# WC.net
KiCad netlist of a schematic drawn in EAGLE
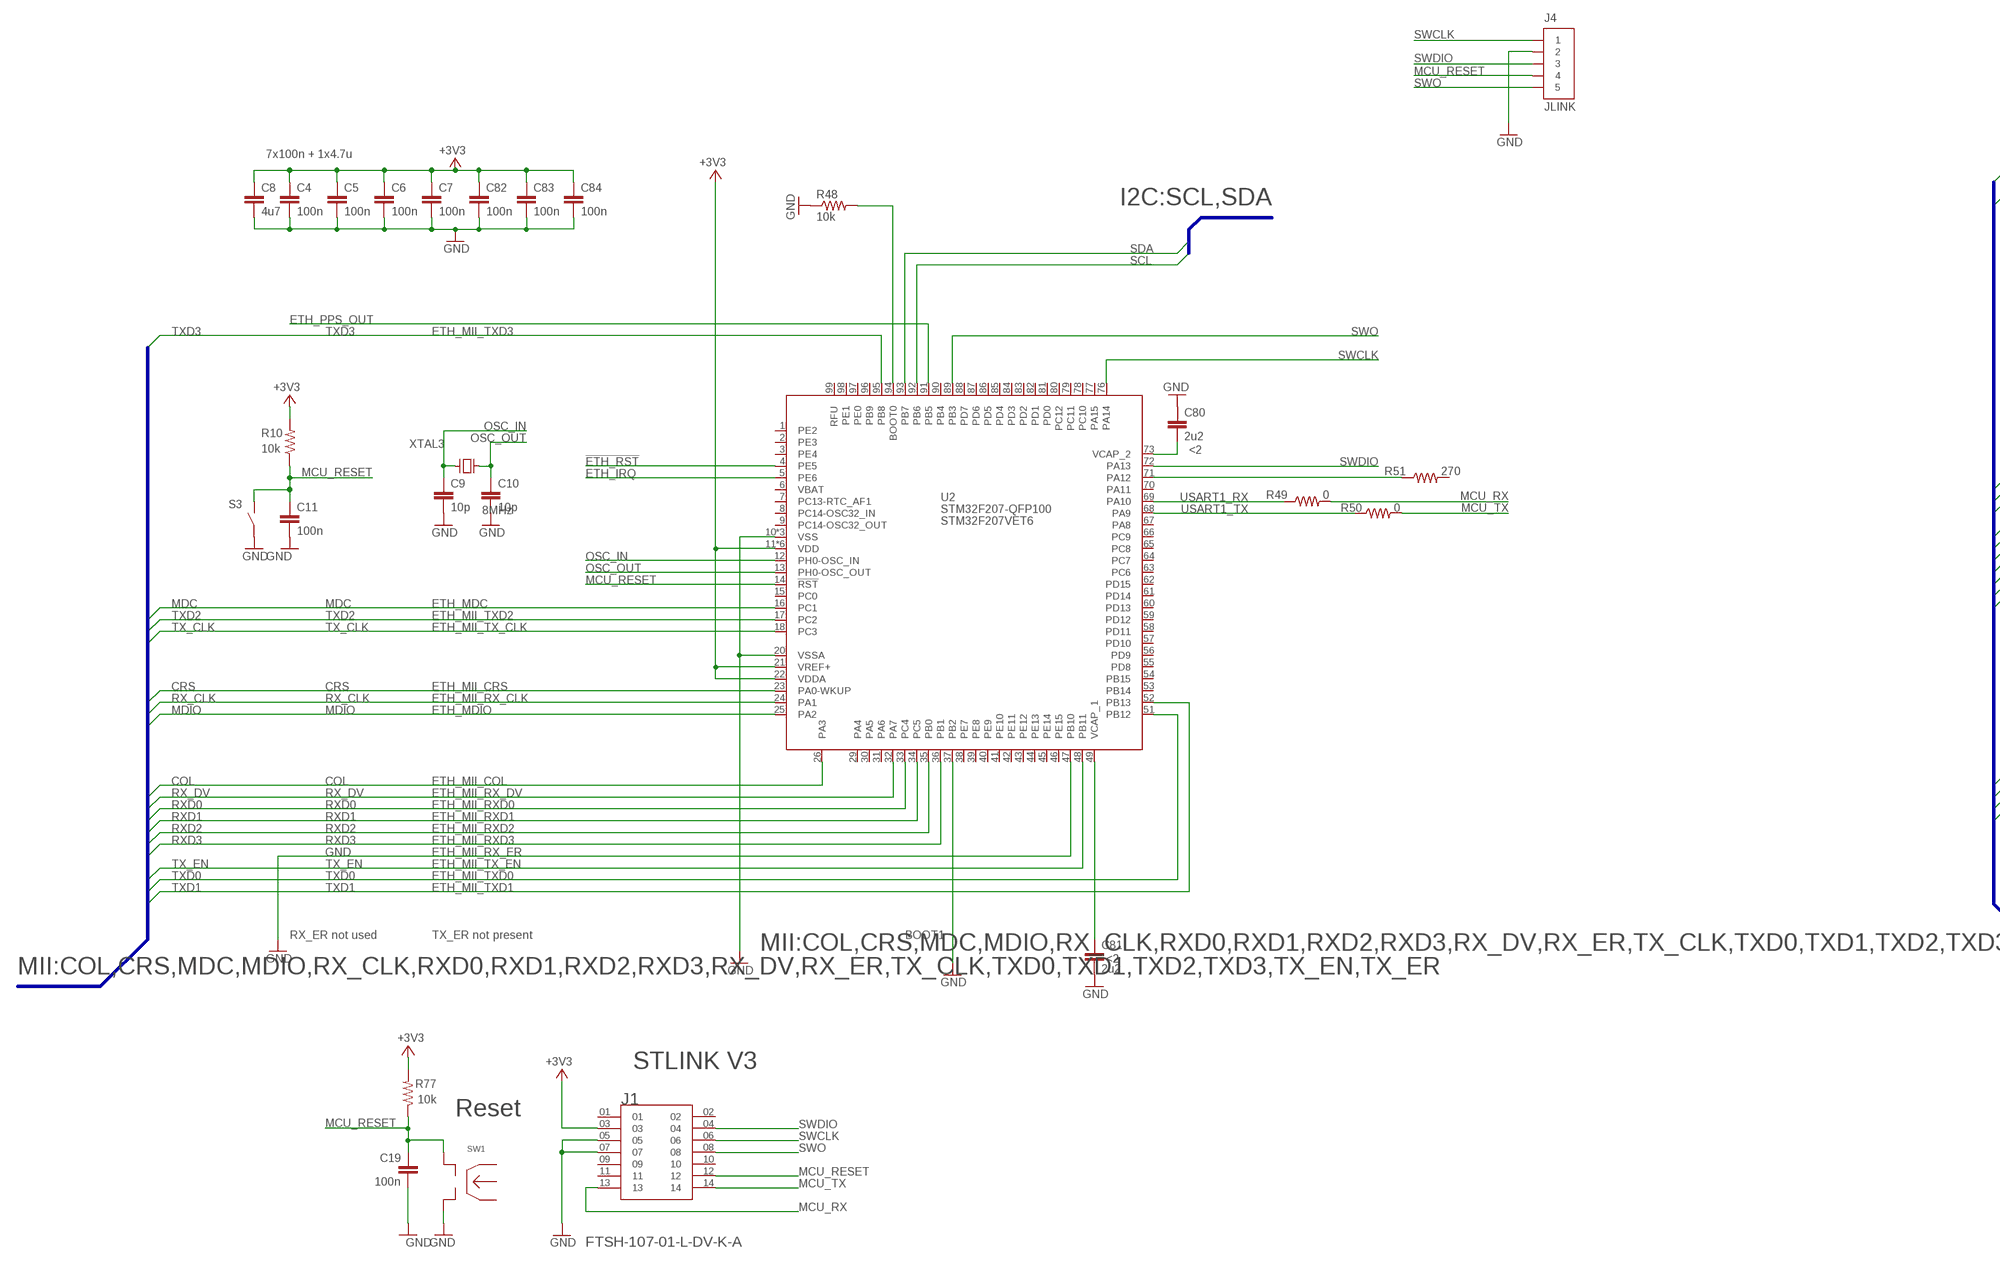
[diagram p0: schematic, sheet 1, part 1 of 2]
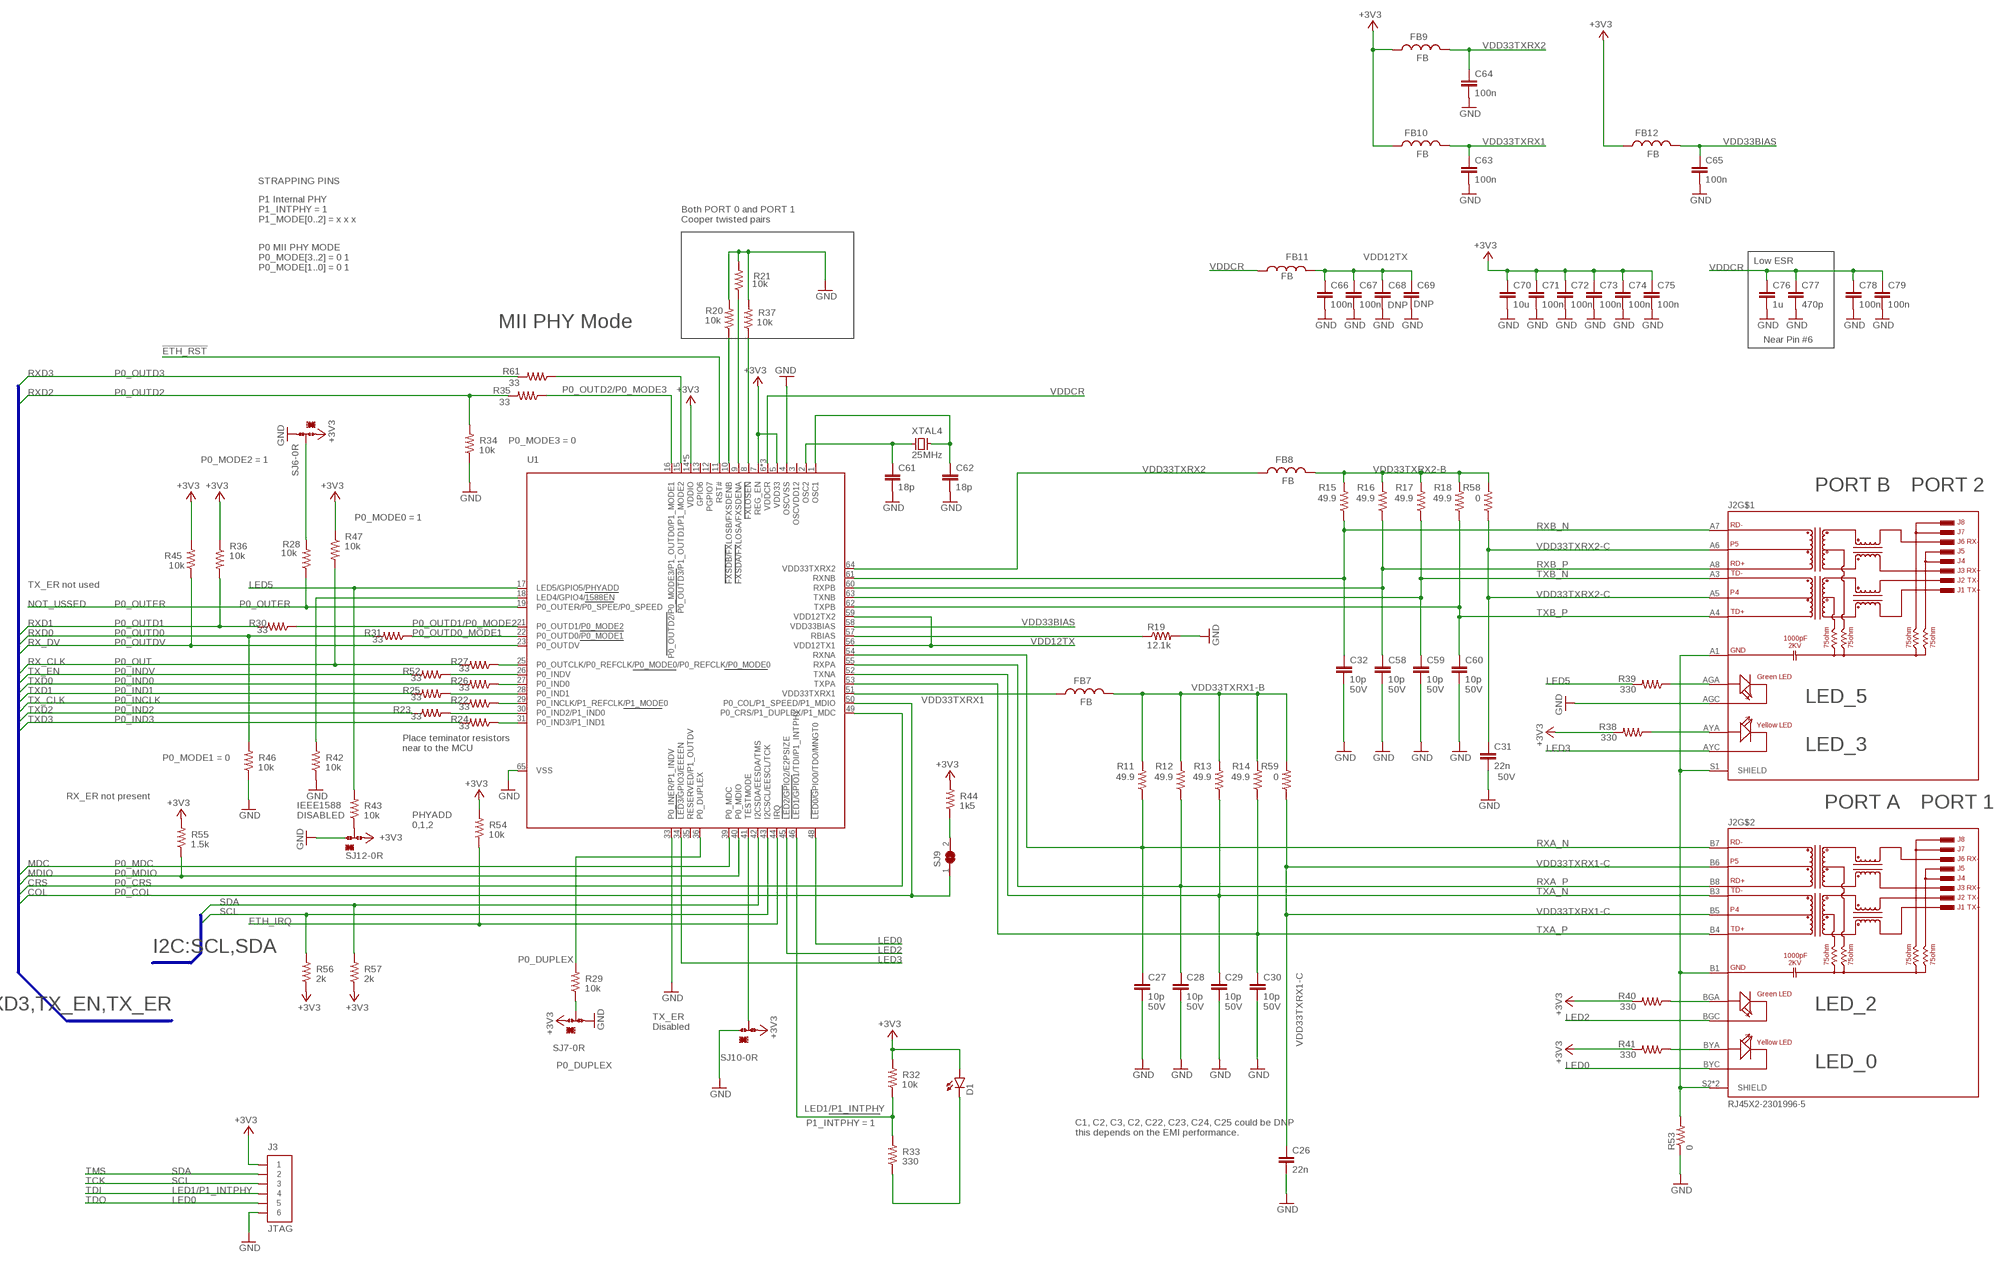
[diagram p1: schematic, sheet 1, part 2 of 2]
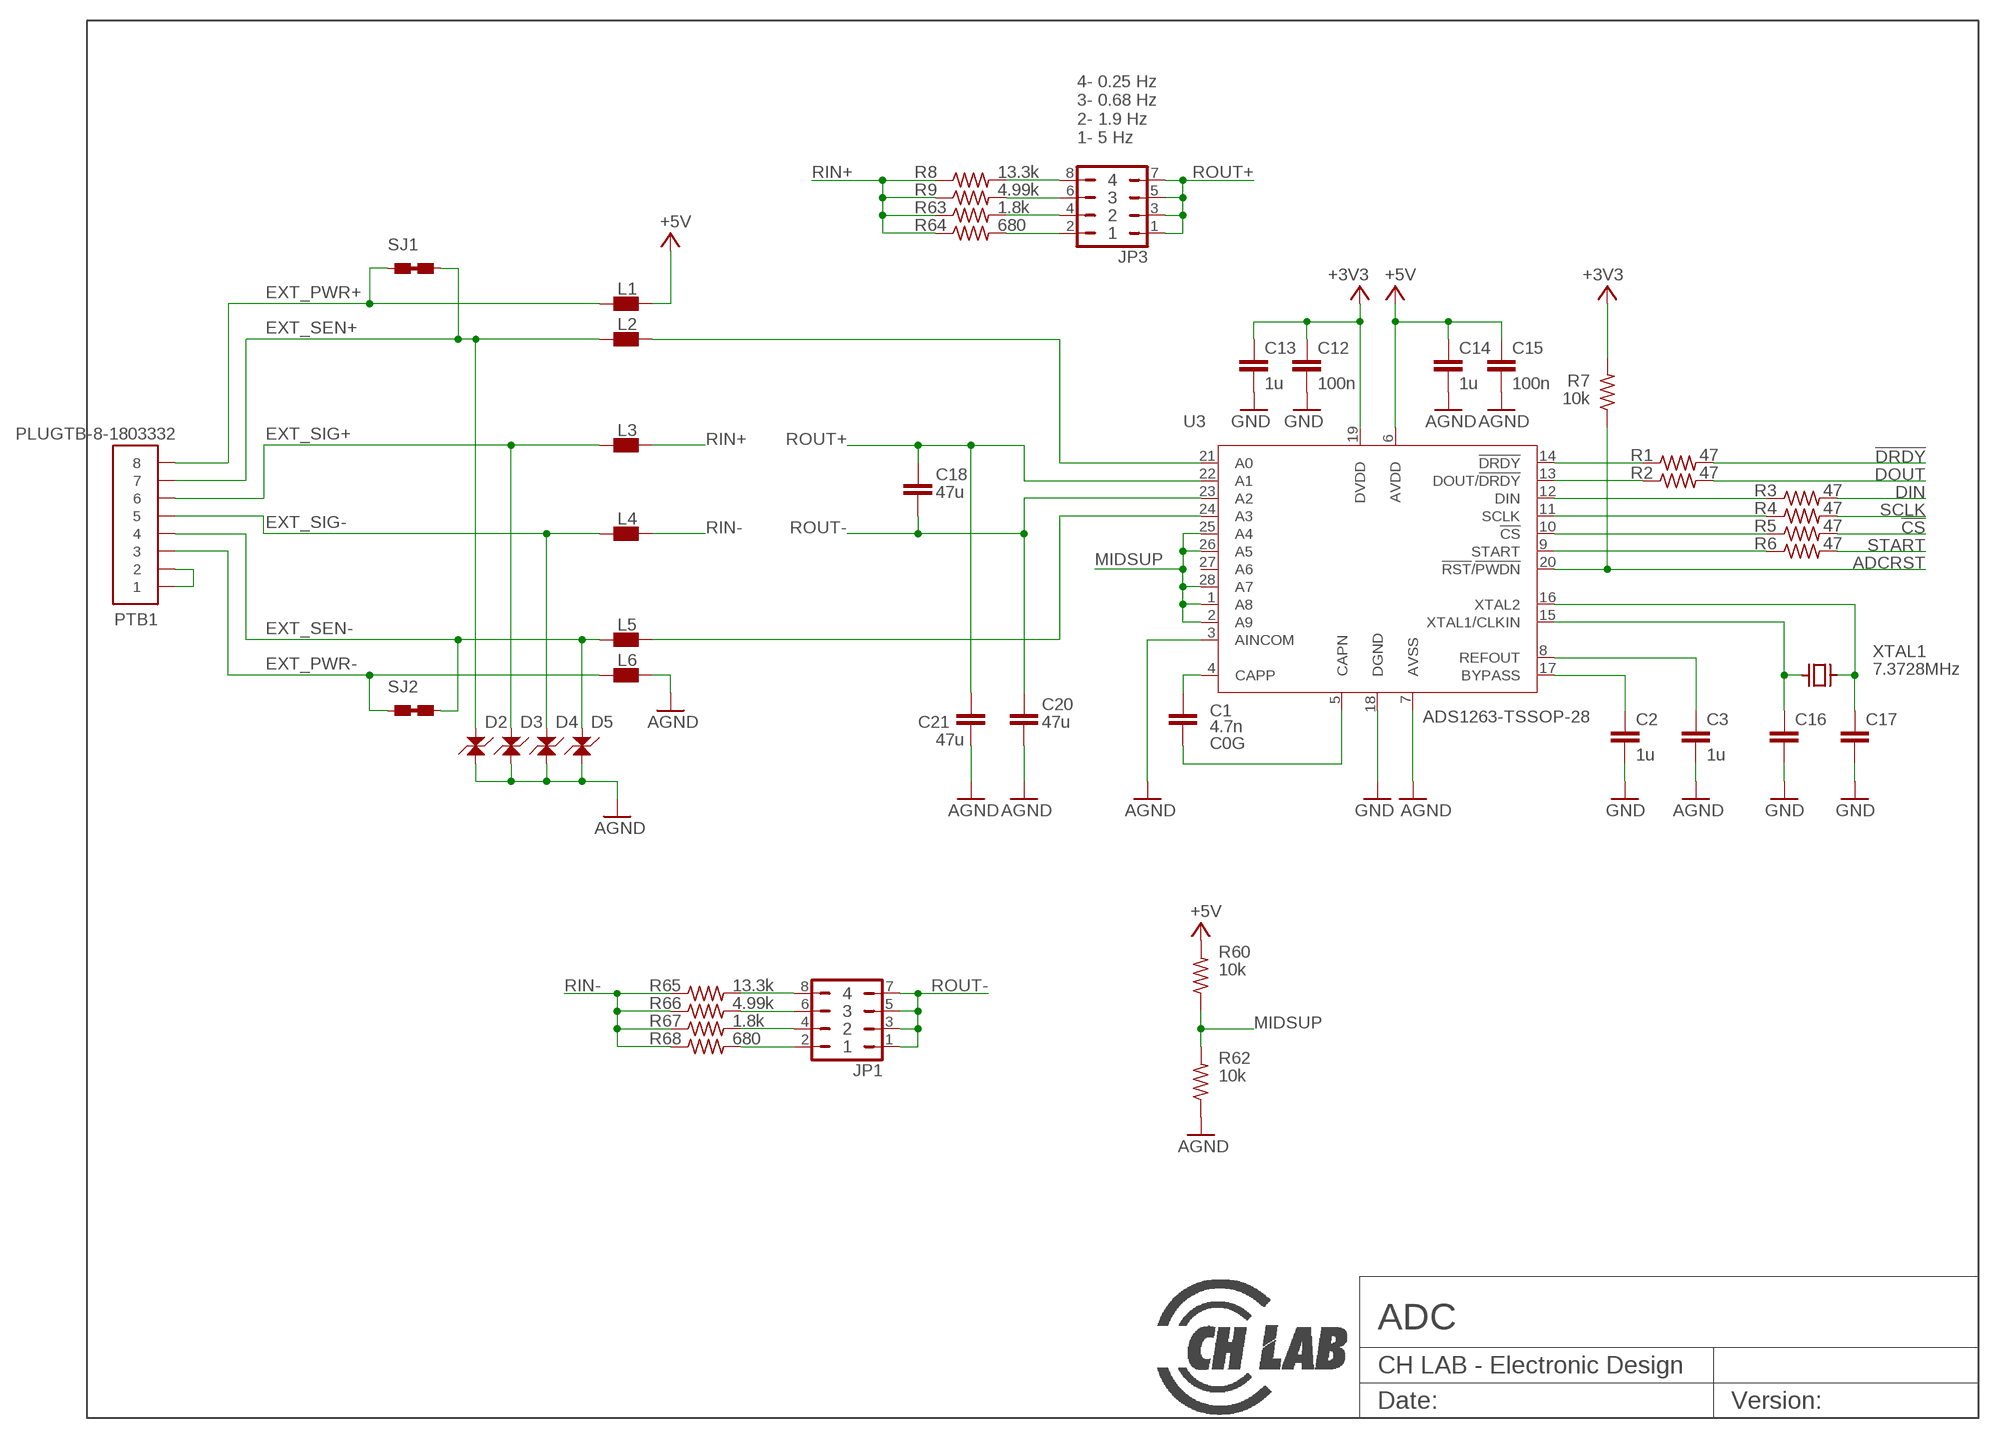
[diagram p2: schematic, sheet 2]

(export (version "E")
  (design (tool "Eeschema 10.0.6"))
  (components
    (comp (ref "C1")
      (value "4.7n")
      (footprint "eagle-import:C_0603")
      (fields (field (name "DK") "C0G"))
      (libsource (lib "eagle-import") (part "C_0603"))
    )
    (comp (ref "C2")
      (value "1u")
      (footprint "eagle-import:C_0603")
      (libsource (lib "eagle-import") (part "C_0603"))
    )
    (comp (ref "C3")
      (value "1u")
      (footprint "eagle-import:C_0603")
      (libsource (lib "eagle-import") (part "C_0603"))
    )
    (comp (ref "C12")
      (value "100n")
      (footprint "eagle-import:C_0603")
      (libsource (lib "eagle-import") (part "C_0603"))
    )
    (comp (ref "C13")
      (value "1u")
      (footprint "eagle-import:C_0603")
      (libsource (lib "eagle-import") (part "C_0603"))
    )
    (comp (ref "C14")
      (value "1u")
      (footprint "eagle-import:C_0603")
      (libsource (lib "eagle-import") (part "C_0603"))
    )
    (comp (ref "C15")
      (value "100n")
      (footprint "eagle-import:C_0603")
      (libsource (lib "eagle-import") (part "C_0603"))
    )
    (comp (ref "C16")
      (value "C_0603")
      (footprint "eagle-import:C_0603")
      (libsource (lib "eagle-import") (part "C_0603"))
    )
    (comp (ref "C17")
      (value "C_0603")
      (footprint "eagle-import:C_0603")
      (libsource (lib "eagle-import") (part "C_0603"))
    )
    (comp (ref "C18")
      (value "47u")
      (footprint "eagle-import:C_1210")
      (libsource (lib "eagle-import") (part "C_1210"))
    )
    (comp (ref "C20")
      (value "47u")
      (footprint "eagle-import:C_1210")
      (libsource (lib "eagle-import") (part "C_1210"))
    )
    (comp (ref "C21")
      (value "47u")
      (footprint "eagle-import:C_1210")
      (libsource (lib "eagle-import") (part "C_1210"))
    )
    (comp (ref "D2")
      (value "LESD5D5.0CT1G")
      (footprint "eagle-import:SOD523")
      (libsource (lib "eagle-import") (part "LESD5D5.0CT1G"))
    )
    (comp (ref "D3")
      (value "LESD5D5.0CT1G")
      (footprint "eagle-import:SOD523")
      (libsource (lib "eagle-import") (part "LESD5D5.0CT1G"))
    )
    (comp (ref "D4")
      (value "LESD5D5.0CT1G")
      (footprint "eagle-import:SOD523")
      (libsource (lib "eagle-import") (part "LESD5D5.0CT1G"))
    )
    (comp (ref "D5")
      (value "LESD5D5.0CT1G")
      (footprint "eagle-import:SOD523")
      (libsource (lib "eagle-import") (part "LESD5D5.0CT1G"))
    )
    (comp (ref "JP1")
      (value "JP4Q")
      (footprint "eagle-import:JP4Q")
      (libsource (lib "eagle-import") (part "JP4Q"))
    )
    (comp (ref "JP3")
      (value "JP4Q")
      (footprint "eagle-import:JP4Q")
      (libsource (lib "eagle-import") (part "JP4Q"))
    )
    (comp (ref "L1")
      (value "FB_0603")
      (footprint "eagle-import:R_0603")
      (libsource (lib "eagle-import") (part "FB_0603"))
    )
    (comp (ref "L2")
      (value "FB_0603")
      (footprint "eagle-import:R_0603")
      (libsource (lib "eagle-import") (part "FB_0603"))
    )
    (comp (ref "L3")
      (value "FB_0603")
      (footprint "eagle-import:R_0603")
      (libsource (lib "eagle-import") (part "FB_0603"))
    )
    (comp (ref "L4")
      (value "FB_0603")
      (footprint "eagle-import:R_0603")
      (libsource (lib "eagle-import") (part "FB_0603"))
    )
    (comp (ref "L5")
      (value "FB_0603")
      (footprint "eagle-import:R_0603")
      (libsource (lib "eagle-import") (part "FB_0603"))
    )
    (comp (ref "L6")
      (value "FB_0603")
      (footprint "eagle-import:R_0603")
      (libsource (lib "eagle-import") (part "FB_0603"))
    )
    (comp (ref "PTB1")
      (value "PLUGTB-8-1803332")
      (footprint "eagle-import:1803332")
      (libsource (lib "eagle-import") (part "PLUGTB-8-1803332"))
    )
    (comp (ref "R1")
      (value "47")
      (footprint "eagle-import:R_0402")
      (libsource (lib "eagle-import") (part "R_0402"))
    )
    (comp (ref "R2")
      (value "47")
      (footprint "eagle-import:R_0402")
      (libsource (lib "eagle-import") (part "R_0402"))
    )
    (comp (ref "R3")
      (value "47")
      (footprint "eagle-import:R_0402")
      (libsource (lib "eagle-import") (part "R_0402"))
    )
    (comp (ref "R4")
      (value "47")
      (footprint "eagle-import:R_0402")
      (libsource (lib "eagle-import") (part "R_0402"))
    )
    (comp (ref "R5")
      (value "47")
      (footprint "eagle-import:R_0402")
      (libsource (lib "eagle-import") (part "R_0402"))
    )
    (comp (ref "R6")
      (value "47")
      (footprint "eagle-import:R_0402")
      (libsource (lib "eagle-import") (part "R_0402"))
    )
    (comp (ref "R7")
      (value "10k")
      (footprint "eagle-import:R_0603")
      (libsource (lib "eagle-import") (part "R_0603"))
    )
    (comp (ref "R8")
      (value "13.3k")
      (footprint "eagle-import:R_0603")
      (libsource (lib "eagle-import") (part "R_0603"))
    )
    (comp (ref "R9")
      (value "4.99k")
      (footprint "eagle-import:R_0603")
      (libsource (lib "eagle-import") (part "R_0603"))
    )
    (comp (ref "R60")
      (value "10k")
      (footprint "eagle-import:R_0603")
      (libsource (lib "eagle-import") (part "R_0603"))
    )
    (comp (ref "R62")
      (value "10k")
      (footprint "eagle-import:R_0603")
      (libsource (lib "eagle-import") (part "R_0603"))
    )
    (comp (ref "R63")
      (value "1.8k")
      (footprint "eagle-import:R_0603")
      (libsource (lib "eagle-import") (part "R_0603"))
    )
    (comp (ref "R64")
      (value "680")
      (footprint "eagle-import:R_0603")
      (libsource (lib "eagle-import") (part "R_0603"))
    )
    (comp (ref "R65")
      (value "13.3k")
      (footprint "eagle-import:R_0603")
      (libsource (lib "eagle-import") (part "R_0603"))
    )
    (comp (ref "R66")
      (value "4.99k")
      (footprint "eagle-import:R_0603")
      (libsource (lib "eagle-import") (part "R_0603"))
    )
    (comp (ref "R67")
      (value "1.8k")
      (footprint "eagle-import:R_0603")
      (libsource (lib "eagle-import") (part "R_0603"))
    )
    (comp (ref "R68")
      (value "680")
      (footprint "eagle-import:R_0603")
      (libsource (lib "eagle-import") (part "R_0603"))
    )
    (comp (ref "SJ1")
      (value "SJUMPER-NC")
      (footprint "eagle-import:SJ1")
      (libsource (lib "eagle-import") (part "SJUMPER-NC"))
    )
    (comp (ref "SJ2")
      (value "SJUMPER-NC")
      (footprint "eagle-import:SJ1")
      (libsource (lib "eagle-import") (part "SJUMPER-NC"))
    )
    (comp (ref "U3")
      (value "ADS1263-TSSOP-28")
      (footprint "eagle-import:SOP65P640X120-28N")
      (libsource (lib "eagle-import") (part "ADS1263-TSSOP-28"))
    )
    (comp (ref "XTAL1")
      (value "7.3728MHz")
      (footprint "eagle-import:XTAL")
      (fields
        (field (name "LINK") "https://www.mouser.com/ProductDetail/ABRACON/ABLS-7.3728MHZ-K4T?qs=uDmhV2jwPReaiEAs5bxjfg%3D%3D")
        (field (name "MPN") "ABLS-7.3728MHZ-K4T")
      )
      (libsource (lib "eagle-import") (part "XTAL-SMD-11.44.8"))
    )
    (comp (ref "C4")
      (value "100n")
      (footprint "eagle-import:C_0603")
      (libsource (lib "eagle-import") (part "C_0603"))
    )
    (comp (ref "C5")
      (value "100n")
      (footprint "eagle-import:C_0603")
      (libsource (lib "eagle-import") (part "C_0603"))
    )
    (comp (ref "C6")
      (value "100n")
      (footprint "eagle-import:C_0603")
      (libsource (lib "eagle-import") (part "C_0603"))
    )
    (comp (ref "C7")
      (value "100n")
      (footprint "eagle-import:C_0603")
      (libsource (lib "eagle-import") (part "C_0603"))
    )
    (comp (ref "C8")
      (value "4u7")
      (footprint "eagle-import:C_0805")
      (libsource (lib "eagle-import") (part "C_0805"))
    )
    (comp (ref "C9")
      (value "10p")
      (footprint "eagle-import:C_0603")
      (libsource (lib "eagle-import") (part "C_0603"))
    )
    (comp (ref "C10")
      (value "10p")
      (footprint "eagle-import:C_0603")
      (libsource (lib "eagle-import") (part "C_0603"))
    )
    (comp (ref "C11")
      (value "100n")
      (footprint "eagle-import:C_0603")
      (libsource (lib "eagle-import") (part "C_0603"))
    )
    (comp (ref "C19")
      (value "100n")
      (footprint "eagle-import:C_0603")
      (libsource (lib "eagle-import") (part "C_0603"))
    )
    (comp (ref "C26")
      (value "22n")
      (footprint "eagle-import:C_0805")
      (libsource (lib "eagle-import") (part "C_0805"))
    )
    (comp (ref "C27")
      (value "10p")
      (footprint "eagle-import:C_0402")
      (fields (field (name "V") "50V"))
      (libsource (lib "eagle-import") (part "C_0402"))
    )
    (comp (ref "C28")
      (value "10p")
      (footprint "eagle-import:C_0402")
      (fields (field (name "V") "50V"))
      (libsource (lib "eagle-import") (part "C_0402"))
    )
    (comp (ref "C29")
      (value "10p")
      (footprint "eagle-import:C_0402")
      (fields (field (name "V") "50V"))
      (libsource (lib "eagle-import") (part "C_0402"))
    )
    (comp (ref "C30")
      (value "10p")
      (footprint "eagle-import:C_0402")
      (fields (field (name "V") "50V"))
      (libsource (lib "eagle-import") (part "C_0402"))
    )
    (comp (ref "C31")
      (value "22n")
      (footprint "eagle-import:C_0805")
      (fields (field (name "VOLTAGE") "50V"))
      (libsource (lib "eagle-import") (part "C_0805"))
    )
    (comp (ref "C32")
      (value "10p")
      (footprint "eagle-import:C_0402")
      (fields (field (name "V") "50V"))
      (libsource (lib "eagle-import") (part "C_0402"))
    )
    (comp (ref "C58")
      (value "10p")
      (footprint "eagle-import:C_0402")
      (fields (field (name "V") "50V"))
      (libsource (lib "eagle-import") (part "C_0402"))
    )
    (comp (ref "C59")
      (value "10p")
      (footprint "eagle-import:C_0402")
      (fields (field (name "V") "50V"))
      (libsource (lib "eagle-import") (part "C_0402"))
    )
    (comp (ref "C60")
      (value "10p")
      (footprint "eagle-import:C_0402")
      (fields (field (name "V") "50V"))
      (libsource (lib "eagle-import") (part "C_0402"))
    )
    (comp (ref "C61")
      (value "18p")
      (footprint "eagle-import:C_0603")
      (libsource (lib "eagle-import") (part "C_0603"))
    )
    (comp (ref "C62")
      (value "18p")
      (footprint "eagle-import:C_0603")
      (libsource (lib "eagle-import") (part "C_0603"))
    )
    (comp (ref "C63")
      (value "100n")
      (footprint "eagle-import:C_0603")
      (libsource (lib "eagle-import") (part "C_0603"))
    )
    (comp (ref "C64")
      (value "100n")
      (footprint "eagle-import:C_0603")
      (libsource (lib "eagle-import") (part "C_0603"))
    )
    (comp (ref "C65")
      (value "100n")
      (footprint "eagle-import:C_0603")
      (libsource (lib "eagle-import") (part "C_0603"))
    )
    (comp (ref "C66")
      (value "100n")
      (footprint "eagle-import:C_0603")
      (libsource (lib "eagle-import") (part "C_0603"))
    )
    (comp (ref "C67")
      (value "100n")
      (footprint "eagle-import:C_0603")
      (libsource (lib "eagle-import") (part "C_0603"))
    )
    (comp (ref "C68")
      (value "100n")
      (footprint "eagle-import:C_0603")
      (fields (field (name "DNP") "DNP"))
      (libsource (lib "eagle-import") (part "C_0603"))
    )
    (comp (ref "C69")
      (value "100n")
      (footprint "eagle-import:C_0603")
      (fields (field (name "DNP") "DNP"))
      (libsource (lib "eagle-import") (part "C_0603"))
    )
    (comp (ref "C70")
      (value "10u")
      (footprint "eagle-import:C_0603")
      (libsource (lib "eagle-import") (part "C_0603"))
    )
    (comp (ref "C71")
      (value "100n")
      (footprint "eagle-import:C_0603")
      (libsource (lib "eagle-import") (part "C_0603"))
    )
    (comp (ref "C72")
      (value "100n")
      (footprint "eagle-import:C_0603")
      (libsource (lib "eagle-import") (part "C_0603"))
    )
    (comp (ref "C73")
      (value "100n")
      (footprint "eagle-import:C_0603")
      (libsource (lib "eagle-import") (part "C_0603"))
    )
    (comp (ref "C74")
      (value "100n")
      (footprint "eagle-import:C_0603")
      (libsource (lib "eagle-import") (part "C_0603"))
    )
    (comp (ref "C75")
      (value "100n")
      (footprint "eagle-import:C_0603")
      (libsource (lib "eagle-import") (part "C_0603"))
    )
    (comp (ref "C76")
      (value "1u")
      (footprint "eagle-import:C_0603")
      (fields (field (name "ERS") "LOW"))
      (libsource (lib "eagle-import") (part "C_0603"))
    )
    (comp (ref "C77")
      (value "470p")
      (footprint "eagle-import:C_0603")
      (libsource (lib "eagle-import") (part "C_0603"))
    )
    (comp (ref "C78")
      (value "100n")
      (footprint "eagle-import:C_0603")
      (libsource (lib "eagle-import") (part "C_0603"))
    )
    (comp (ref "C79")
      (value "100n")
      (footprint "eagle-import:C_0603")
      (libsource (lib "eagle-import") (part "C_0603"))
    )
    (comp (ref "C80")
      (value "2u2")
      (footprint "eagle-import:C_0603")
      (fields (field (name "ERS") "<2"))
      (libsource (lib "eagle-import") (part "C_0603"))
    )
    (comp (ref "C81")
      (value "2u2")
      (footprint "eagle-import:C_0603")
      (fields (field (name "ERS") "<2"))
      (libsource (lib "eagle-import") (part "C_0603"))
    )
    (comp (ref "C82")
      (value "100n")
      (footprint "eagle-import:C_0603")
      (libsource (lib "eagle-import") (part "C_0603"))
    )
    (comp (ref "C83")
      (value "100n")
      (footprint "eagle-import:C_0603")
      (libsource (lib "eagle-import") (part "C_0603"))
    )
    (comp (ref "C84")
      (value "100n")
      (footprint "eagle-import:C_0603")
      (libsource (lib "eagle-import") (part "C_0603"))
    )
    (comp (ref "D1")
      (value "LED_0603_ARROW")
      (footprint "eagle-import:LED_0603_ARROW")
      (libsource (lib "eagle-import") (part "LED_0603_ARROW"))
    )
    (comp (ref "FB7")
      (value "FB")
      (footprint "eagle-import:L_0603")
      (libsource (lib "eagle-import") (part "L_0603"))
    )
    (comp (ref "FB8")
      (value "FB")
      (footprint "eagle-import:L_0603")
      (libsource (lib "eagle-import") (part "L_0603"))
    )
    (comp (ref "FB9")
      (value "FB")
      (footprint "eagle-import:L_0603")
      (libsource (lib "eagle-import") (part "L_0603"))
    )
    (comp (ref "FB10")
      (value "FB")
      (footprint "eagle-import:L_0603")
      (libsource (lib "eagle-import") (part "L_0603"))
    )
    (comp (ref "FB11")
      (value "FB")
      (footprint "eagle-import:L_0603")
      (libsource (lib "eagle-import") (part "L_0603"))
    )
    (comp (ref "FB12")
      (value "FB")
      (footprint "eagle-import:L_0603")
      (libsource (lib "eagle-import") (part "L_0603"))
    )
    (comp (ref "J1")
      (value "FTSH-107-01-L-DV-K-A")
      (footprint "eagle-import:SAMTEC_FTSH-107-01-L-DV-K-A")
      (fields (field (name "MANUFACTURER") "Samtec"))
      (libsource (lib "eagle-import") (part "FTSH-107-01-L-DV-K-A"))
    )
    (comp (ref "J2")
      (value "RJ45X2-2301996-5")
      (footprint "eagle-import:2301996-5")
      (libsource (lib "eagle-import") (part "RJ45X2-2301996-5"))
    )
    (comp (ref "J3")
      (value "JTAG")
      (footprint "eagle-import:CONN-VERT-2.54MM-6PINS-2ROWS")
      (libsource (lib "eagle-import") (part "CONVERT-2X3-2.54MM-MALE2.54MM"))
    )
    (comp (ref "J4")
      (value "CONVERT-1X5-2.54MM-MALE_HOLES")
      (footprint "eagle-import:1X05")
      (libsource (lib "eagle-import") (part "CONVERT-1X5-2.54MM-MALE_HOLES"))
    )
    (comp (ref "R10")
      (value "10k")
      (footprint "eagle-import:R_0603")
      (libsource (lib "eagle-import") (part "R_0603"))
    )
    (comp (ref "R11")
      (value "49.9")
      (footprint "eagle-import:R_0402")
      (libsource (lib "eagle-import") (part "R_0402"))
    )
    (comp (ref "R12")
      (value "49.9")
      (footprint "eagle-import:R_0402")
      (libsource (lib "eagle-import") (part "R_0402"))
    )
    (comp (ref "R13")
      (value "49.9")
      (footprint "eagle-import:R_0402")
      (libsource (lib "eagle-import") (part "R_0402"))
    )
    (comp (ref "R14")
      (value "49.9")
      (footprint "eagle-import:R_0402")
      (libsource (lib "eagle-import") (part "R_0402"))
    )
    (comp (ref "R15")
      (value "49.9")
      (footprint "eagle-import:R_0402")
      (libsource (lib "eagle-import") (part "R_0402"))
    )
    (comp (ref "R16")
      (value "49.9")
      (footprint "eagle-import:R_0402")
      (libsource (lib "eagle-import") (part "R_0402"))
    )
    (comp (ref "R17")
      (value "49.9")
      (footprint "eagle-import:R_0402")
      (libsource (lib "eagle-import") (part "R_0402"))
    )
    (comp (ref "R18")
      (value "49.9")
      (footprint "eagle-import:R_0402")
      (libsource (lib "eagle-import") (part "R_0402"))
    )
    (comp (ref "R19")
      (value "12.1k")
      (footprint "eagle-import:R_0603")
      (libsource (lib "eagle-import") (part "R_0603"))
    )
    (comp (ref "R20")
      (value "10k")
      (footprint "eagle-import:R_0603")
      (libsource (lib "eagle-import") (part "R_0603"))
    )
    (comp (ref "R21")
      (value "10k")
      (footprint "eagle-import:R_0603")
      (libsource (lib "eagle-import") (part "R_0603"))
    )
    (comp (ref "R22")
      (value "33")
      (footprint "eagle-import:R_0603")
      (libsource (lib "eagle-import") (part "R_0603"))
    )
    (comp (ref "R23")
      (value "33")
      (footprint "eagle-import:R_0603")
      (libsource (lib "eagle-import") (part "R_0603"))
    )
    (comp (ref "R24")
      (value "33")
      (footprint "eagle-import:R_0603")
      (libsource (lib "eagle-import") (part "R_0603"))
    )
    (comp (ref "R25")
      (value "33")
      (footprint "eagle-import:R_0603")
      (libsource (lib "eagle-import") (part "R_0603"))
    )
    (comp (ref "R26")
      (value "33")
      (footprint "eagle-import:R_0603")
      (libsource (lib "eagle-import") (part "R_0603"))
    )
    (comp (ref "R27")
      (value "33")
      (footprint "eagle-import:R_0603")
      (libsource (lib "eagle-import") (part "R_0603"))
    )
    (comp (ref "R28")
      (value "10k")
      (footprint "eagle-import:R_0603")
      (libsource (lib "eagle-import") (part "R_0603"))
    )
    (comp (ref "R29")
      (value "10k")
      (footprint "eagle-import:R_0603")
      (libsource (lib "eagle-import") (part "R_0603"))
    )
    (comp (ref "R30")
      (value "33")
      (footprint "eagle-import:R_0603")
      (libsource (lib "eagle-import") (part "R_0603"))
    )
    (comp (ref "R31")
      (value "33")
      (footprint "eagle-import:R_0603")
      (libsource (lib "eagle-import") (part "R_0603"))
    )
    (comp (ref "R32")
      (value "10k")
      (footprint "eagle-import:R_0603")
      (libsource (lib "eagle-import") (part "R_0603"))
    )
    (comp (ref "R33")
      (value "330")
      (footprint "eagle-import:R_0603")
      (libsource (lib "eagle-import") (part "R_0603"))
    )
    (comp (ref "R34")
      (value "10k")
      (footprint "eagle-import:R_0603")
      (libsource (lib "eagle-import") (part "R_0603"))
    )
    (comp (ref "R35")
      (value "33")
      (footprint "eagle-import:R_0603")
      (libsource (lib "eagle-import") (part "R_0603"))
    )
    (comp (ref "R36")
      (value "10k")
      (footprint "eagle-import:R_0603")
      (libsource (lib "eagle-import") (part "R_0603"))
    )
    (comp (ref "R37")
      (value "10k")
      (footprint "eagle-import:R_0603")
      (libsource (lib "eagle-import") (part "R_0603"))
    )
    (comp (ref "R38")
      (value "330")
      (footprint "eagle-import:R_0603")
      (libsource (lib "eagle-import") (part "R_0603"))
    )
    (comp (ref "R39")
      (value "330")
      (footprint "eagle-import:R_0603")
      (libsource (lib "eagle-import") (part "R_0603"))
    )
    (comp (ref "R40")
      (value "330")
      (footprint "eagle-import:R_0603")
      (libsource (lib "eagle-import") (part "R_0603"))
    )
    (comp (ref "R41")
      (value "330")
      (footprint "eagle-import:R_0603")
      (libsource (lib "eagle-import") (part "R_0603"))
    )
    (comp (ref "R42")
      (value "10k")
      (footprint "eagle-import:R_0603")
      (libsource (lib "eagle-import") (part "R_0603"))
    )
    (comp (ref "R43")
      (value "10k")
      (footprint "eagle-import:R_0603")
      (libsource (lib "eagle-import") (part "R_0603"))
    )
    (comp (ref "R44")
      (value "1k5")
      (footprint "eagle-import:R_0603")
      (libsource (lib "eagle-import") (part "R_0603"))
    )
    (comp (ref "R45")
      (value "10k")
      (footprint "eagle-import:R_0603")
      (libsource (lib "eagle-import") (part "R_0603"))
    )
    (comp (ref "R46")
      (value "10k")
      (footprint "eagle-import:R_0603")
      (libsource (lib "eagle-import") (part "R_0603"))
    )
    (comp (ref "R47")
      (value "10k")
      (footprint "eagle-import:R_0603")
      (libsource (lib "eagle-import") (part "R_0603"))
    )
    (comp (ref "R48")
      (value "10k")
      (footprint "eagle-import:R_0603")
      (libsource (lib "eagle-import") (part "R_0603"))
    )
    (comp (ref "R49")
      (value "0")
      (footprint "eagle-import:R_0603")
      (libsource (lib "eagle-import") (part "R_0603"))
    )
    (comp (ref "R50")
      (value "0")
      (footprint "eagle-import:R_0603")
      (libsource (lib "eagle-import") (part "R_0603"))
    )
    (comp (ref "R51")
      (value "270")
      (footprint "eagle-import:R_0603")
      (libsource (lib "eagle-import") (part "R_0603"))
    )
    (comp (ref "R52")
      (value "33")
      (footprint "eagle-import:R_0603")
      (libsource (lib "eagle-import") (part "R_0603"))
    )
    (comp (ref "R53")
      (value "0")
      (footprint "eagle-import:R_1206")
      (libsource (lib "eagle-import") (part "R_1206"))
    )
    (comp (ref "R54")
      (value "10k")
      (footprint "eagle-import:R_0603")
      (libsource (lib "eagle-import") (part "R_0603"))
    )
    (comp (ref "R55")
      (value "1.5k")
      (footprint "eagle-import:R_0603")
      (libsource (lib "eagle-import") (part "R_0603"))
    )
    (comp (ref "R56")
      (value "2k")
      (footprint "eagle-import:R_0603")
      (libsource (lib "eagle-import") (part "R_0603"))
    )
    (comp (ref "R57")
      (value "2k")
      (footprint "eagle-import:R_0603")
      (libsource (lib "eagle-import") (part "R_0603"))
    )
    (comp (ref "R58")
      (value "0")
      (footprint "eagle-import:R_0402")
      (libsource (lib "eagle-import") (part "R_0402"))
    )
    (comp (ref "R59")
      (value "0")
      (footprint "eagle-import:R_0402")
      (libsource (lib "eagle-import") (part "R_0402"))
    )
    (comp (ref "R61")
      (value "33")
      (footprint "eagle-import:R_0603")
      (libsource (lib "eagle-import") (part "R_0603"))
    )
    (comp (ref "R77")
      (value "10k")
      (footprint "eagle-import:R_0603")
      (libsource (lib "eagle-import") (part "R_0603"))
    )
    (comp (ref "S3")
      (value "TSWITCH_SMTR2")
      (footprint "eagle-import:SMTR2")
      (libsource (lib "eagle-import") (part "TSWITCH_SMTR2"))
    )
    (comp (ref "SJ6")
      (value "attributre")
      (footprint "eagle-import:A0R-JMP")
      (libsource (lib "eagle-import") (part "0R-JUMPA"))
    )
    (comp (ref "SJ7")
      (value "0R-JUMPA")
      (footprint "eagle-import:A0R-JMP")
      (libsource (lib "eagle-import") (part "0R-JUMPA"))
    )
    (comp (ref "SJ9") (value "SJ") (footprint "eagle-import:SJ") (libsource (lib "eagle-import") (part "SJ")))
    (comp (ref "SJ10")
      (value "0R-JUMPA")
      (footprint "eagle-import:A0R-JMP")
      (libsource (lib "eagle-import") (part "0R-JUMPA"))
    )
    (comp (ref "SJ12")
      (value "0R-JUMPA")
      (footprint "eagle-import:A0R-JMP")
      (libsource (lib "eagle-import") (part "0R-JUMPA"))
    )
    (comp (ref "SW1")
      (value "SWITCH-SCREW")
      (footprint "eagle-import:SCREW-SWITCH")
      (libsource (lib "eagle-import") (part "SWITCH-SCREW"))
    )
    (comp (ref "U1")
      (value "LAN9353")
      (footprint "eagle-import:QFN50P900X900X100-65T600N")
      (libsource (lib "eagle-import") (part "LAN9353-64QFN"))
    )
    (comp (ref "U2")
      (value "STM32F207-QFP100")
      (footprint "eagle-import:QFP50P1600X1600X160-100N")
      (fields (field (name "MPN") "STM32F207VET6 "))
      (libsource (lib "eagle-import") (part "STM32F207-QFP100"))
    )
    (comp (ref "XTAL3")
      (value "8MHz")
      (footprint "eagle-import:XTAL3.2X2.5")
      (fields (field (name "MPN") "830108313809"))
      (libsource (lib "eagle-import") (part "XTAL3.2X2.5"))
    )
    (comp (ref "XTAL4")
      (value "25MHz")
      (footprint "eagle-import:XTAL3.2X2.5")
      (libsource (lib "eagle-import") (part "XTAL3.2X2.5"))
    )
  )
  (nets
    (net (code "5") (name "+3V3") (class "Default")
      (node (ref "C12") (pin "P$1") (pinfunction "1_P$1") (pintype "passive"))
      (node (ref "C13") (pin "P$1") (pinfunction "1_P$1") (pintype "passive"))
      (node (ref "C4") (pin "P$1") (pinfunction "1_P$1") (pintype "passive"))
      (node (ref "C5") (pin "P$1") (pinfunction "1_P$1") (pintype "passive"))
      (node (ref "C6") (pin "P$1") (pinfunction "1_P$1") (pintype "passive"))
      (node (ref "C7") (pin "P$1") (pinfunction "1_P$1") (pintype "passive"))
      (node (ref "C70") (pin "P$1") (pinfunction "1_P$1") (pintype "passive"))
      (node (ref "C71") (pin "P$1") (pinfunction "1_P$1") (pintype "passive"))
      (node (ref "C72") (pin "P$1") (pinfunction "1_P$1") (pintype "passive"))
      (node (ref "C73") (pin "P$1") (pinfunction "1_P$1") (pintype "passive"))
      (node (ref "C74") (pin "P$1") (pinfunction "1_P$1") (pintype "passive"))
      (node (ref "C75") (pin "P$1") (pinfunction "1_P$1") (pintype "passive"))
      (node (ref "C8") (pin "P$1") (pinfunction "1_P$1") (pintype "passive"))
      (node (ref "C82") (pin "P$1") (pinfunction "1_P$1") (pintype "passive"))
      (node (ref "C83") (pin "P$1") (pinfunction "1_P$1") (pintype "passive"))
      (node (ref "C84") (pin "P$1") (pinfunction "1_P$1") (pintype "passive"))
      (node (ref "D1") (pin "A") (pinfunction "A_A") (pintype "passive"))
      (node (ref "FB10") (pin "2") (pinfunction "2_2") (pintype "passive"))
      (node (ref "FB12") (pin "2") (pinfunction "2_2") (pintype "passive"))
      (node (ref "FB9") (pin "2") (pinfunction "2_2") (pintype "passive"))
      (node (ref "J1") (pin "03") (pinfunction "03_03") (pintype "passive"))
      (node (ref "J3") (pin "1") (pinfunction "1_1") (pintype "bidirectional"))
      (node (ref "R10") (pin "2") (pinfunction "2_2") (pintype "passive"))
      (node (ref "R32") (pin "2") (pinfunction "2_2") (pintype "passive"))
      (node (ref "R36") (pin "1") (pinfunction "1_1") (pintype "passive"))
      (node (ref "R38") (pin "2") (pinfunction "2_2") (pintype "passive"))
      (node (ref "R40") (pin "2") (pinfunction "2_2") (pintype "passive"))
      (node (ref "R41") (pin "2") (pinfunction "2_2") (pintype "passive"))
      (node (ref "R44") (pin "2") (pinfunction "2_2") (pintype "passive"))
      (node (ref "R45") (pin "2") (pinfunction "2_2") (pintype "passive"))
      (node (ref "R47") (pin "1") (pinfunction "1_1") (pintype "passive"))
      (node (ref "R54") (pin "2") (pinfunction "2_2") (pintype "passive"))
      (node (ref "R55") (pin "2") (pinfunction "2_2") (pintype "passive"))
      (node (ref "R56") (pin "1") (pinfunction "1_1") (pintype "passive"))
      (node (ref "R57") (pin "1") (pinfunction "1_1") (pintype "passive"))
      (node (ref "R7") (pin "2") (pinfunction "2_2") (pintype "passive"))
      (node (ref "R77") (pin "2") (pinfunction "2_2") (pintype "passive"))
      (node (ref "SJ10") (pin "3") (pinfunction "3_3") (pintype "passive"))
      (node (ref "SJ12") (pin "3") (pinfunction "3_3") (pintype "passive"))
      (node (ref "SJ6") (pin "1") (pinfunction "1_1") (pintype "passive"))
      (node (ref "SJ7") (pin "1") (pinfunction "1_1") (pintype "passive"))
      (node (ref "U1") (pin "14") (pinfunction "VDDIO_14") (pintype "bidirectional"))
      (node (ref "U1") (pin "20") (pinfunction "VDDIO_20") (pintype "bidirectional"))
      (node (ref "U1") (pin "32") (pinfunction "VDDIO_32") (pintype "bidirectional"))
      (node (ref "U1") (pin "37") (pinfunction "VDDIO_37") (pintype "bidirectional"))
      (node (ref "U1") (pin "47") (pinfunction "VDDIO_47") (pintype "bidirectional"))
      (node (ref "U1") (pin "5") (pinfunction "VDD33_5") (pintype "bidirectional"))
      (node (ref "U1") (pin "7") (pinfunction "REG_EN_7") (pintype "bidirectional"))
      (node (ref "U2") (pin "100") (pinfunction "VDD_100") (pintype "bidirectional"))
      (node (ref "U2") (pin "11") (pinfunction "VDD_11") (pintype "bidirectional"))
      (node (ref "U2") (pin "19") (pinfunction "VDD_19") (pintype "bidirectional"))
      (node (ref "U2") (pin "21") (pinfunction "VREF+_21") (pintype "bidirectional"))
      (node (ref "U2") (pin "22") (pinfunction "VDDA_22") (pintype "bidirectional"))
      (node (ref "U2") (pin "28") (pinfunction "VDD_28") (pintype "bidirectional"))
      (node (ref "U2") (pin "50") (pinfunction "VDD_50") (pintype "bidirectional"))
      (node (ref "U2") (pin "75") (pinfunction "VDD_75") (pintype "bidirectional"))
      (node (ref "U3") (pin "19") (pinfunction "DVDD_19") (pintype "power_in"))
    )
    (net (code "6") (name "+5V") (class "Default")
      (node (ref "C14") (pin "P$1") (pinfunction "1_P$1") (pintype "passive"))
      (node (ref "C15") (pin "P$1") (pinfunction "1_P$1") (pintype "passive"))
      (node (ref "L1") (pin "2") (pinfunction "2_2") (pintype "passive"))
      (node (ref "R60") (pin "2") (pinfunction "2_2") (pintype "passive"))
      (node (ref "U3") (pin "6") (pinfunction "AVDD_6") (pintype "power_in"))
    )
    (net (code "9") (name "ADCRST") (class "Default")
      (node (ref "R7") (pin "1") (pinfunction "1_1") (pintype "passive"))
      (node (ref "U3") (pin "20") (pinfunction "~{RST}/~{PWDN}_20") (pintype "input"))
    )
    (net (code "10") (name "AGND") (class "Default")
      (node (ref "C14") (pin "P$2") (pinfunction "2_P$2") (pintype "passive"))
      (node (ref "C15") (pin "P$2") (pinfunction "2_P$2") (pintype "passive"))
      (node (ref "C20") (pin "P$1") (pinfunction "1_P$1") (pintype "passive"))
      (node (ref "C21") (pin "P$1") (pinfunction "1_P$1") (pintype "passive"))
      (node (ref "C3") (pin "P$2") (pinfunction "2_P$2") (pintype "passive"))
      (node (ref "D2") (pin "C") (pinfunction "P$2_C") (pintype "bidirectional"))
      (node (ref "D3") (pin "C") (pinfunction "P$2_C") (pintype "bidirectional"))
      (node (ref "D4") (pin "C") (pinfunction "P$2_C") (pintype "bidirectional"))
      (node (ref "D5") (pin "C") (pinfunction "P$2_C") (pintype "bidirectional"))
      (node (ref "L6") (pin "2") (pinfunction "2_2") (pintype "passive"))
      (node (ref "R62") (pin "1") (pinfunction "1_1") (pintype "passive"))
      (node (ref "U3") (pin "3") (pinfunction "AINCOM_3") (pintype "bidirectional"))
      (node (ref "U3") (pin "7") (pinfunction "AVSS_7") (pintype "power_in"))
    )
    (net (code "11") (name "COL") (class "Default")
      (node (ref "SJ9") (pin "1") (pinfunction "1_1") (pintype "passive"))
      (node (ref "U1") (pin "50") (pinfunction "P0_COL/P1_SPEED/P1_MDIO_50") (pintype "bidirectional"))
      (node (ref "U2") (pin "26") (pinfunction "PA3_26") (pintype "bidirectional"))
    )
    (net (code "12") (name "CRS") (class "Default")
      (node (ref "U1") (pin "49") (pinfunction "P0_CRS/P1_DUPLEX/P1_MDC_49") (pintype "bidirectional"))
      (node (ref "U2") (pin "23") (pinfunction "PA0-WKUP_23") (pintype "bidirectional"))
    )
    (net (code "13") (name "DIN") (class "Default")
      (node (ref "R3") (pin "2") (pinfunction "2_2") (pintype "passive"))
    )
    (net (code "14") (name "DOUT") (class "Default")
      (node (ref "R2") (pin "2") (pinfunction "2_2") (pintype "passive"))
    )
    (net (code "15") (name "ETH_IRQ") (class "Default")
      (node (ref "R54") (pin "1") (pinfunction "1_1") (pintype "passive"))
      (node (ref "U1") (pin "44") (pinfunction "IRQ_44") (pintype "bidirectional"))
      (node (ref "U2") (pin "5") (pinfunction "PE6_5") (pintype "bidirectional"))
    )
    (net (code "16") (name "ETH_PPS_OUT") (class "Default")
      (node (ref "U2") (pin "91") (pinfunction "PB5_91") (pintype "bidirectional"))
    )
    (net (code "17") (name "EXT_PWR+") (class "Default")
      (node (ref "L1") (pin "1") (pinfunction "1_1") (pintype "passive"))
      (node (ref "PTB1") (pin "P$8") (pinfunction "8_P$8") (pintype "bidirectional"))
      (node (ref "SJ1") (pin "P$1") (pinfunction "P$1_P$1") (pintype "bidirectional"))
    )
    (net (code "18") (name "EXT_PWR-") (class "Default")
      (node (ref "L6") (pin "1") (pinfunction "1_1") (pintype "passive"))
      (node (ref "PTB1") (pin "P$3") (pinfunction "3_P$3") (pintype "bidirectional"))
      (node (ref "SJ2") (pin "P$1") (pinfunction "P$1_P$1") (pintype "bidirectional"))
    )
    (net (code "19") (name "EXT_SEN+") (class "Default")
      (node (ref "D2") (pin "A") (pinfunction "P$1_A") (pintype "bidirectional"))
      (node (ref "L2") (pin "1") (pinfunction "1_1") (pintype "passive"))
      (node (ref "PTB1") (pin "P$7") (pinfunction "7_P$7") (pintype "bidirectional"))
      (node (ref "SJ1") (pin "P$2") (pinfunction "P$2_P$2") (pintype "bidirectional"))
    )
    (net (code "20") (name "EXT_SEN-") (class "Default")
      (node (ref "D5") (pin "A") (pinfunction "P$1_A") (pintype "bidirectional"))
      (node (ref "L5") (pin "1") (pinfunction "1_1") (pintype "passive"))
      (node (ref "PTB1") (pin "P$4") (pinfunction "4_P$4") (pintype "bidirectional"))
      (node (ref "SJ2") (pin "P$2") (pinfunction "P$2_P$2") (pintype "bidirectional"))
    )
    (net (code "21") (name "EXT_SIG+") (class "Default")
      (node (ref "D3") (pin "A") (pinfunction "P$1_A") (pintype "bidirectional"))
      (node (ref "L3") (pin "1") (pinfunction "1_1") (pintype "passive"))
      (node (ref "PTB1") (pin "P$6") (pinfunction "6_P$6") (pintype "bidirectional"))
    )
    (net (code "22") (name "EXT_SIG-") (class "Default")
      (node (ref "D4") (pin "A") (pinfunction "P$1_A") (pintype "bidirectional"))
      (node (ref "L4") (pin "1") (pinfunction "1_1") (pintype "passive"))
      (node (ref "PTB1") (pin "P$5") (pinfunction "5_P$5") (pintype "bidirectional"))
    )
    (net (code "23") (name "GND") (class "Default")
      (node (ref "C10") (pin "P$2") (pinfunction "2_P$2") (pintype "passive"))
      (node (ref "C11") (pin "P$2") (pinfunction "2_P$2") (pintype "passive"))
      (node (ref "C12") (pin "P$2") (pinfunction "2_P$2") (pintype "passive"))
      (node (ref "C13") (pin "P$2") (pinfunction "2_P$2") (pintype "passive"))
      (node (ref "C16") (pin "P$2") (pinfunction "2_P$2") (pintype "passive"))
      (node (ref "C17") (pin "P$2") (pinfunction "2_P$2") (pintype "passive"))
      (node (ref "C19") (pin "P$2") (pinfunction "2_P$2") (pintype "passive"))
      (node (ref "C2") (pin "P$2") (pinfunction "2_P$2") (pintype "passive"))
      (node (ref "C26") (pin "P$2") (pinfunction "2_P$2") (pintype "passive"))
      (node (ref "C27") (pin "P$2") (pinfunction "2_P$2") (pintype "passive"))
      (node (ref "C28") (pin "P$2") (pinfunction "2_P$2") (pintype "passive"))
      (node (ref "C29") (pin "P$2") (pinfunction "2_P$2") (pintype "passive"))
      (node (ref "C30") (pin "P$2") (pinfunction "2_P$2") (pintype "passive"))
      (node (ref "C31") (pin "P$2") (pinfunction "2_P$2") (pintype "passive"))
      (node (ref "C32") (pin "P$2") (pinfunction "2_P$2") (pintype "passive"))
      (node (ref "C4") (pin "P$2") (pinfunction "2_P$2") (pintype "passive"))
      (node (ref "C5") (pin "P$2") (pinfunction "2_P$2") (pintype "passive"))
      (node (ref "C58") (pin "P$2") (pinfunction "2_P$2") (pintype "passive"))
      (node (ref "C59") (pin "P$2") (pinfunction "2_P$2") (pintype "passive"))
      (node (ref "C6") (pin "P$2") (pinfunction "2_P$2") (pintype "passive"))
      (node (ref "C60") (pin "P$2") (pinfunction "2_P$2") (pintype "passive"))
      (node (ref "C61") (pin "P$2") (pinfunction "2_P$2") (pintype "passive"))
      (node (ref "C62") (pin "P$2") (pinfunction "2_P$2") (pintype "passive"))
      (node (ref "C63") (pin "P$2") (pinfunction "2_P$2") (pintype "passive"))
      (node (ref "C64") (pin "P$2") (pinfunction "2_P$2") (pintype "passive"))
      (node (ref "C65") (pin "P$2") (pinfunction "2_P$2") (pintype "passive"))
      (node (ref "C66") (pin "P$2") (pinfunction "2_P$2") (pintype "passive"))
      (node (ref "C67") (pin "P$2") (pinfunction "2_P$2") (pintype "passive"))
      (node (ref "C68") (pin "P$2") (pinfunction "2_P$2") (pintype "passive"))
      (node (ref "C69") (pin "P$2") (pinfunction "2_P$2") (pintype "passive"))
      (node (ref "C7") (pin "P$2") (pinfunction "2_P$2") (pintype "passive"))
      (node (ref "C70") (pin "P$2") (pinfunction "2_P$2") (pintype "passive"))
      (node (ref "C71") (pin "P$2") (pinfunction "2_P$2") (pintype "passive"))
      (node (ref "C72") (pin "P$2") (pinfunction "2_P$2") (pintype "passive"))
      (node (ref "C73") (pin "P$2") (pinfunction "2_P$2") (pintype "passive"))
      (node (ref "C74") (pin "P$2") (pinfunction "2_P$2") (pintype "passive"))
      (node (ref "C75") (pin "P$2") (pinfunction "2_P$2") (pintype "passive"))
      (node (ref "C76") (pin "P$2") (pinfunction "2_P$2") (pintype "passive"))
      (node (ref "C77") (pin "P$2") (pinfunction "2_P$2") (pintype "passive"))
      (node (ref "C78") (pin "P$2") (pinfunction "2_P$2") (pintype "passive"))
      (node (ref "C79") (pin "P$2") (pinfunction "2_P$2") (pintype "passive"))
      (node (ref "C8") (pin "P$2") (pinfunction "2_P$2") (pintype "passive"))
      (node (ref "C80") (pin "P$1") (pinfunction "1_P$1") (pintype "passive"))
      (node (ref "C81") (pin "P$2") (pinfunction "2_P$2") (pintype "passive"))
      (node (ref "C82") (pin "P$2") (pinfunction "2_P$2") (pintype "passive"))
      (node (ref "C83") (pin "P$2") (pinfunction "2_P$2") (pintype "passive"))
      (node (ref "C84") (pin "P$2") (pinfunction "2_P$2") (pintype "passive"))
      (node (ref "C9") (pin "P$2") (pinfunction "2_P$2") (pintype "passive"))
      (node (ref "J1") (pin "05") (pinfunction "05_05") (pintype "passive"))
      (node (ref "J1") (pin "07") (pinfunction "07_07") (pintype "passive"))
      (node (ref "J2") (pin "AGC") (pinfunction "GC_AGC") (pintype "passive"))
      (node (ref "J3") (pin "6") (pinfunction "6_6") (pintype "bidirectional"))
      (node (ref "J4") (pin "2") (pinfunction "2_2") (pintype "bidirectional"))
      (node (ref "R19") (pin "2") (pinfunction "2_2") (pintype "passive"))
      (node (ref "R20") (pin "2") (pinfunction "2_2") (pintype "passive"))
      (node (ref "R21") (pin "2") (pinfunction "2_2") (pintype "passive"))
      (node (ref "R34") (pin "1") (pinfunction "1_1") (pintype "passive"))
      (node (ref "R37") (pin "2") (pinfunction "2_2") (pintype "passive"))
      (node (ref "R42") (pin "1") (pinfunction "1_1") (pintype "passive"))
      (node (ref "R46") (pin "1") (pinfunction "1_1") (pintype "passive"))
      (node (ref "R48") (pin "1") (pinfunction "1_1") (pintype "passive"))
      (node (ref "R53") (pin "1") (pinfunction "1_1") (pintype "passive"))
      (node (ref "S3") (pin "P$1") (pinfunction "P$1_P$1") (pintype "bidirectional"))
      (node (ref "S3") (pin "P$2") (pinfunction "P$1_P$2") (pintype "bidirectional"))
      (node (ref "SJ10") (pin "1") (pinfunction "1_1") (pintype "passive"))
      (node (ref "SJ12") (pin "1") (pinfunction "1_1") (pintype "passive"))
      (node (ref "SJ6") (pin "3") (pinfunction "3_3") (pintype "passive"))
      (node (ref "SJ7") (pin "3") (pinfunction "3_3") (pintype "passive"))
      (node (ref "SW1") (pin "2") (pinfunction "P$2_2") (pintype "bidirectional"))
      (node (ref "U1") (pin "33") (pinfunction "P0_INER/P1_INDV_33") (pintype "bidirectional"))
      (node (ref "U1") (pin "4") (pinfunction "OSCVSS_4") (pintype "bidirectional"))
      (node (ref "U1") (pin "65") (pinfunction "VSS_65") (pintype "bidirectional"))
      (node (ref "U2") (pin "10") (pinfunction "VSS_10") (pintype "bidirectional"))
      (node (ref "U2") (pin "20") (pinfunction "VSSA_20") (pintype "bidirectional"))
      (node (ref "U2") (pin "27") (pinfunction "VSS_27") (pintype "bidirectional"))
      (node (ref "U2") (pin "37") (pinfunction "PB2_37") (pintype "bidirectional"))
      (node (ref "U2") (pin "47") (pinfunction "PB10_47") (pintype "bidirectional"))
      (node (ref "U2") (pin "74") (pinfunction "VSS_74") (pintype "bidirectional"))
      (node (ref "U3") (pin "18") (pinfunction "DGND_18") (pintype "power_in"))
    )
    (net (code "24") (name "LED0") (class "Default")
      (node (ref "J2") (pin "BYC") (pinfunction "YC_BYC") (pintype "passive"))
      (node (ref "J3") (pin "5") (pinfunction "5_5") (pintype "bidirectional"))
      (node (ref "U1") (pin "48") (pinfunction "LED0/GPIO0/TDO/MNGT0_48") (pintype "bidirectional"))
    )
    (net (code "25") (name "LED1{slash}P1_INTPHY") (class "Default")
      (node (ref "J3") (pin "4") (pinfunction "4_4") (pintype "bidirectional"))
      (node (ref "R32") (pin "1") (pinfunction "1_1") (pintype "passive"))
      (node (ref "R33") (pin "2") (pinfunction "2_2") (pintype "passive"))
      (node (ref "U1") (pin "46") (pinfunction "LED1/GPIO1/TDI/P1_INTPHY_46") (pintype "bidirectional"))
    )
    (net (code "26") (name "LED2") (class "Default")
      (node (ref "J2") (pin "BGC") (pinfunction "GC_BGC") (pintype "passive"))
      (node (ref "U1") (pin "45") (pinfunction "LED2/GPIO2/E2PSIZE_45") (pintype "bidirectional"))
    )
    (net (code "27") (name "LED3") (class "Default")
      (node (ref "J2") (pin "AYC") (pinfunction "YC_AYC") (pintype "passive"))
      (node (ref "U1") (pin "34") (pinfunction "LED3/GPIO3/EEEEN_34") (pintype "bidirectional"))
    )
    (net (code "28") (name "LED5") (class "Default")
      (node (ref "R39") (pin "2") (pinfunction "2_2") (pintype "passive"))
      (node (ref "R43") (pin "2") (pinfunction "2_2") (pintype "passive"))
      (node (ref "U1") (pin "17") (pinfunction "LED5/GPIO5/PHYADD_17") (pintype "bidirectional"))
    )
    (net (code "29") (name "MCU_RESET") (class "Default")
      (node (ref "C11") (pin "P$1") (pinfunction "1_P$1") (pintype "passive"))
      (node (ref "C19") (pin "P$1") (pinfunction "1_P$1") (pintype "passive"))
      (node (ref "J1") (pin "12") (pinfunction "12_12") (pintype "passive"))
      (node (ref "J4") (pin "4") (pinfunction "4_4") (pintype "bidirectional"))
      (node (ref "R10") (pin "1") (pinfunction "1_1") (pintype "passive"))
      (node (ref "R77") (pin "1") (pinfunction "1_1") (pintype "passive"))
      (node (ref "S3") (pin "P$3") (pinfunction "P$2_P$3") (pintype "bidirectional"))
      (node (ref "S3") (pin "P$4") (pinfunction "P$2_P$4") (pintype "bidirectional"))
      (node (ref "SW1") (pin "1") (pinfunction "P$1_1") (pintype "bidirectional"))
      (node (ref "U2") (pin "14") (pinfunction "~{RST}_14") (pintype "bidirectional"))
    )
    (net (code "30") (name "MCU_RX") (class "Default")
      (node (ref "J1") (pin "13") (pinfunction "13_13") (pintype "passive"))
      (node (ref "R49") (pin "2") (pinfunction "2_2") (pintype "passive"))
    )
    (net (code "31") (name "MCU_TX") (class "Default")
      (node (ref "J1") (pin "14") (pinfunction "14_14") (pintype "passive"))
      (node (ref "R50") (pin "2") (pinfunction "2_2") (pintype "passive"))
    )
    (net (code "32") (name "MDC") (class "Default")
      (node (ref "U1") (pin "39") (pinfunction "P0_MDC_39") (pintype "bidirectional"))
      (node (ref "U2") (pin "16") (pinfunction "PC1_16") (pintype "bidirectional"))
    )
    (net (code "33") (name "MDIO") (class "Default")
      (node (ref "R55") (pin "1") (pinfunction "1_1") (pintype "passive"))
      (node (ref "U1") (pin "40") (pinfunction "P0_MDIO_40") (pintype "bidirectional"))
      (node (ref "U2") (pin "25") (pinfunction "PA2_25") (pintype "bidirectional"))
    )
    (net (code "34") (name "MIDSUP") (class "Default")
      (node (ref "R60") (pin "1") (pinfunction "1_1") (pintype "passive"))
      (node (ref "R62") (pin "2") (pinfunction "2_2") (pintype "passive"))
      (node (ref "U3") (pin "1") (pinfunction "A8_1") (pintype "bidirectional"))
      (node (ref "U3") (pin "2") (pinfunction "A9_2") (pintype "bidirectional"))
      (node (ref "U3") (pin "25") (pinfunction "A4_25") (pintype "bidirectional"))
      (node (ref "U3") (pin "26") (pinfunction "A5_26") (pintype "bidirectional"))
      (node (ref "U3") (pin "28") (pinfunction "A7_28") (pintype "bidirectional"))
    )
    (net (code "35") (name "Net-(C1-1)") (class "Default")
      (node (ref "C1") (pin "P$1") (pinfunction "1_P$1") (pintype "passive"))
      (node (ref "U3") (pin "4") (pinfunction "CAPP_4") (pintype "output"))
    )
    (net (code "36") (name "Net-(C1-2)") (class "Default")
      (node (ref "C1") (pin "P$2") (pinfunction "2_P$2") (pintype "passive"))
      (node (ref "U3") (pin "5") (pinfunction "CAPN_5") (pintype "output"))
    )
    (net (code "37") (name "Net-(C2-1)") (class "Default")
      (node (ref "C2") (pin "P$1") (pinfunction "1_P$1") (pintype "passive"))
      (node (ref "U3") (pin "17") (pinfunction "BYPASS_17") (pintype "output"))
    )
    (net (code "38") (name "Net-(C3-1)") (class "Default")
      (node (ref "C3") (pin "P$1") (pinfunction "1_P$1") (pintype "passive"))
      (node (ref "U3") (pin "8") (pinfunction "REFOUT_8") (pintype "output"))
    )
    (net (code "39") (name "Net-(C16-1)") (class "Default")
      (node (ref "C16") (pin "P$1") (pinfunction "1_P$1") (pintype "passive"))
      (node (ref "U3") (pin "15") (pinfunction "XTAL1/CLKIN_15") (pintype "input"))
      (node (ref "XTAL1") (pin "1") (pinfunction "X1_1") (pintype "passive"))
    )
    (net (code "40") (name "Net-(C17-1)") (class "Default")
      (node (ref "C17") (pin "P$1") (pinfunction "1_P$1") (pintype "passive"))
      (node (ref "U3") (pin "16") (pinfunction "XTAL2_16") (pintype "input"))
      (node (ref "XTAL1") (pin "2") (pinfunction "X2_2") (pintype "passive"))
    )
    (net (code "41") (name "Net-(C61-1)") (class "Default")
      (node (ref "C61") (pin "P$1") (pinfunction "1_P$1") (pintype "passive"))
      (node (ref "U1") (pin "2") (pinfunction "OSC2_2") (pintype "bidirectional"))
      (node (ref "XTAL4") (pin "P$1") (pinfunction "X1_P$1") (pintype "passive"))
    )
    (net (code "42") (name "Net-(C62-1)") (class "Default")
      (node (ref "C62") (pin "P$1") (pinfunction "1_P$1") (pintype "passive"))
      (node (ref "U1") (pin "1") (pinfunction "OSC1_1") (pintype "bidirectional"))
      (node (ref "XTAL4") (pin "P$3") (pinfunction "X2_P$3") (pintype "passive"))
    )
    (net (code "43") (name "Net-(C80-2)") (class "Default")
      (node (ref "C80") (pin "P$2") (pinfunction "2_P$2") (pintype "passive"))
      (node (ref "U2") (pin "73") (pinfunction "VCAP_2_73") (pintype "bidirectional"))
    )
    (net (code "44") (name "Net-(C81-1)") (class "Default")
      (node (ref "C81") (pin "P$1") (pinfunction "1_P$1") (pintype "passive"))
      (node (ref "U2") (pin "49") (pinfunction "VCAP_1_49") (pintype "bidirectional"))
    )
    (net (code "45") (name "Net-(D1-PadK)") (class "Default")
      (node (ref "D1") (pin "K") (pinfunction "K_K") (pintype "passive"))
      (node (ref "R33") (pin "1") (pinfunction "1_1") (pintype "passive"))
    )
    (net (code "46") (name "Net-(J2A-GA)") (class "Default")
      (node (ref "J2") (pin "AGA") (pinfunction "GA_AGA") (pintype "passive"))
      (node (ref "R39") (pin "1") (pinfunction "1_1") (pintype "passive"))
    )
    (net (code "47") (name "Net-(J2A-GND)") (class "Default")
      (node (ref "J2") (pin "A1") (pinfunction "GND_A1") (pintype "power_in"))
      (node (ref "J2") (pin "B1") (pinfunction "GND_B1") (pintype "power_in"))
      (node (ref "J2") (pin "S1") (pinfunction "SHIELD_S1") (pintype "passive"))
      (node (ref "J2") (pin "S2") (pinfunction "SHIELD_S2") (pintype "passive"))
      (node (ref "J2") (pin "S3") (pinfunction "SHIELD_S3") (pintype "passive"))
      (node (ref "R53") (pin "2") (pinfunction "2_2") (pintype "passive"))
    )
    (net (code "48") (name "Net-(J2A-YA)") (class "Default")
      (node (ref "J2") (pin "AYA") (pinfunction "YA_AYA") (pintype "passive"))
      (node (ref "R38") (pin "1") (pinfunction "1_1") (pintype "passive"))
    )
    (net (code "49") (name "Net-(J2B-GA)") (class "Default")
      (node (ref "J2") (pin "BGA") (pinfunction "GA_BGA") (pintype "passive"))
      (node (ref "R40") (pin "1") (pinfunction "1_1") (pintype "passive"))
    )
    (net (code "50") (name "Net-(J2B-YA)") (class "Default")
      (node (ref "J2") (pin "BYA") (pinfunction "YA_BYA") (pintype "passive"))
      (node (ref "R41") (pin "1") (pinfunction "1_1") (pintype "passive"))
    )
    (net (code "51") (name "Net-(JP1-Pad2)") (class "Default")
      (node (ref "JP1") (pin "2") (pinfunction "2_2") (pintype "passive"))
      (node (ref "R68") (pin "2") (pinfunction "2_2") (pintype "passive"))
    )
    (net (code "52") (name "Net-(JP1-Pad4)") (class "Default")
      (node (ref "JP1") (pin "4") (pinfunction "4_4") (pintype "passive"))
      (node (ref "R67") (pin "2") (pinfunction "2_2") (pintype "passive"))
    )
    (net (code "53") (name "Net-(JP1-Pad6)") (class "Default")
      (node (ref "JP1") (pin "6") (pinfunction "6_6") (pintype "passive"))
      (node (ref "R66") (pin "2") (pinfunction "2_2") (pintype "passive"))
    )
    (net (code "54") (name "Net-(JP1-Pad8)") (class "Default")
      (node (ref "JP1") (pin "8") (pinfunction "8_8") (pintype "passive"))
      (node (ref "R65") (pin "2") (pinfunction "2_2") (pintype "passive"))
    )
    (net (code "55") (name "Net-(JP3-Pad2)") (class "Default")
      (node (ref "JP3") (pin "2") (pinfunction "2_2") (pintype "passive"))
      (node (ref "R64") (pin "2") (pinfunction "2_2") (pintype "passive"))
    )
    (net (code "56") (name "Net-(JP3-Pad4)") (class "Default")
      (node (ref "JP3") (pin "4") (pinfunction "4_4") (pintype "passive"))
      (node (ref "R63") (pin "2") (pinfunction "2_2") (pintype "passive"))
    )
    (net (code "57") (name "Net-(JP3-Pad6)") (class "Default")
      (node (ref "JP3") (pin "6") (pinfunction "6_6") (pintype "passive"))
      (node (ref "R9") (pin "2") (pinfunction "2_2") (pintype "passive"))
    )
    (net (code "58") (name "Net-(JP3-Pad8)") (class "Default")
      (node (ref "JP3") (pin "8") (pinfunction "8_8") (pintype "passive"))
      (node (ref "R8") (pin "2") (pinfunction "2_2") (pintype "passive"))
    )
    (net (code "59") (name "Net-(PTB1-1)") (class "Default")
      (node (ref "PTB1") (pin "P$1") (pinfunction "1_P$1") (pintype "bidirectional"))
      (node (ref "PTB1") (pin "P$2") (pinfunction "2_P$2") (pintype "bidirectional"))
    )
    (net (code "60") (name "Net-(R28-Pad2)") (class "Default")
      (node (ref "R28") (pin "2") (pinfunction "2_2") (pintype "passive"))
      (node (ref "SJ6") (pin "2") (pinfunction "2_2") (pintype "passive"))
    )
    (net (code "61") (name "Net-(R29-Pad1)") (class "Default")
      (node (ref "R29") (pin "1") (pinfunction "1_1") (pintype "passive"))
      (node (ref "SJ7") (pin "2") (pinfunction "2_2") (pintype "passive"))
    )
    (net (code "62") (name "Net-(R43-Pad1)") (class "Default")
      (node (ref "R43") (pin "1") (pinfunction "1_1") (pintype "passive"))
      (node (ref "SJ12") (pin "2") (pinfunction "2_2") (pintype "passive"))
    )
    (net (code "63") (name "Net-(R44-Pad1)") (class "Default")
      (node (ref "R44") (pin "1") (pinfunction "1_1") (pintype "passive"))
      (node (ref "SJ9") (pin "2") (pinfunction "2_2") (pintype "passive"))
    )
    (net (code "64") (name "Net-(U1-FXLOSEN)") (class "Default")
      (node (ref "R37") (pin "1") (pinfunction "1_1") (pintype "passive"))
      (node (ref "U1") (pin "8") (pinfunction "FXLOSEN_8") (pintype "bidirectional"))
    )
    (net (code "65") (name "Net-(U1-FXSDA{slash}FXLOSA{slash}FXSDENA)") (class "Default")
      (node (ref "R21") (pin "1") (pinfunction "1_1") (pintype "passive"))
      (node (ref "U1") (pin "9") (pinfunction "FXSDA/FXLOSA/FXSDENA_9") (pintype "bidirectional"))
    )
    (net (code "66") (name "Net-(U1-FXSDB{slash}FXLOSB{slash}FXSDENB)") (class "Default")
      (node (ref "R20") (pin "1") (pinfunction "1_1") (pintype "passive"))
      (node (ref "U1") (pin "10") (pinfunction "FXSDB/FXLOSB/FXSDENB_10") (pintype "bidirectional"))
    )
    (net (code "67") (name "Net-(U1-LED4{slash}GPIO4{slash}1588EN)") (class "Default")
      (node (ref "R42") (pin "2") (pinfunction "2_2") (pintype "passive"))
      (node (ref "U1") (pin "18") (pinfunction "LED4/GPIO4/1588EN_18") (pintype "bidirectional"))
    )
    (net (code "68") (name "Net-(U1-P0_INCLK{slash}P1_REFCLK{slash}P1_MODE0)") (class "Default")
      (node (ref "R22") (pin "1") (pinfunction "1_1") (pintype "passive"))
      (node (ref "U1") (pin "29") (pinfunction "P0_INCLK/P1_REFCLK/P1_MODE0_29") (pintype "bidirectional"))
    )
    (net (code "69") (name "Net-(U1-P0_IND0)") (class "Default")
      (node (ref "R26") (pin "1") (pinfunction "1_1") (pintype "passive"))
      (node (ref "U1") (pin "27") (pinfunction "P0_IND0_27") (pintype "bidirectional"))
    )
    (net (code "70") (name "Net-(U1-P0_IND1)") (class "Default")
      (node (ref "R25") (pin "1") (pinfunction "1_1") (pintype "passive"))
      (node (ref "U1") (pin "28") (pinfunction "P0_IND1_28") (pintype "bidirectional"))
    )
    (net (code "71") (name "Net-(U1-P0_IND2{slash}P1_IND0)") (class "Default")
      (node (ref "R23") (pin "1") (pinfunction "1_1") (pintype "passive"))
      (node (ref "U1") (pin "30") (pinfunction "P0_IND2/P1_IND0_30") (pintype "bidirectional"))
    )
    (net (code "72") (name "Net-(U1-P0_IND3{slash}P1_IND1)") (class "Default")
      (node (ref "R24") (pin "1") (pinfunction "1_1") (pintype "passive"))
      (node (ref "U1") (pin "31") (pinfunction "P0_IND3/P1_IND1_31") (pintype "bidirectional"))
    )
    (net (code "73") (name "Net-(U1-P0_INDV)") (class "Default")
      (node (ref "R52") (pin "1") (pinfunction "1_1") (pintype "passive"))
      (node (ref "U1") (pin "26") (pinfunction "P0_INDV_26") (pintype "bidirectional"))
    )
    (net (code "74") (name "Net-(U1-P0_OUTCLK{slash}P0_REFCLK{slash}P0_MODE0{slash}P0_REFCLK{slash}P0_MODE0)") (class "Default")
      (node (ref "R27") (pin "1") (pinfunction "1_1") (pintype "passive"))
      (node (ref "U1") (pin "25") (pinfunction "P0_OUTCLK/P0_REFCLK/P0_MODE0/P0_REFCLK/P0_MODE0_25") (pintype "bidirectional"))
    )
    (net (code "75") (name "Net-(U1-P0_OUTD3{slash}P1_OUTD1{slash}P1_MODE2)") (class "Default")
      (node (ref "R61") (pin "1") (pinfunction "1_1") (pintype "passive"))
      (node (ref "U1") (pin "15") (pinfunction "P0_OUTD3/P1_OUTD1/P1_MODE2_15") (pintype "bidirectional"))
    )
    (net (code "76") (name "Net-(U1-RBIAS)") (class "Default")
      (node (ref "R19") (pin "1") (pinfunction "1_1") (pintype "passive"))
      (node (ref "U1") (pin "57") (pinfunction "RBIAS_57") (pintype "bidirectional"))
    )
    (net (code "77") (name "Net-(U1-TESTMODE)") (class "Default")
      (node (ref "SJ10") (pin "2") (pinfunction "2_2") (pintype "passive"))
      (node (ref "U1") (pin "41") (pinfunction "TESTMODE_41") (pintype "bidirectional"))
    )
    (net (code "78") (name "Net-(U2-BOOT0)") (class "Default")
      (node (ref "R48") (pin "2") (pinfunction "2_2") (pintype "passive"))
      (node (ref "U2") (pin "94") (pinfunction "BOOT0_94") (pintype "bidirectional"))
    )
    (net (code "79") (name "Net-(U2-PA12)") (class "Default")
      (node (ref "R51") (pin "1") (pinfunction "1_1") (pintype "passive"))
      (node (ref "U2") (pin "71") (pinfunction "PA12_71") (pintype "bidirectional"))
    )
    (net (code "80") (name "Net-(U3-A0)") (class "Default")
      (node (ref "L2") (pin "2") (pinfunction "2_2") (pintype "passive"))
      (node (ref "U3") (pin "21") (pinfunction "A0_21") (pintype "bidirectional"))
    )
    (net (code "81") (name "Net-(U3-A3)") (class "Default")
      (node (ref "L5") (pin "2") (pinfunction "2_2") (pintype "passive"))
      (node (ref "U3") (pin "24") (pinfunction "A3_24") (pintype "bidirectional"))
    )
    (net (code "82") (name "Net-(U3-DIN)") (class "Default")
      (node (ref "R3") (pin "1") (pinfunction "1_1") (pintype "passive"))
      (node (ref "U3") (pin "12") (pinfunction "DIN_12") (pintype "input"))
    )
    (net (code "83") (name "Net-(U3-DOUT{slash}~{DRDY})") (class "Default")
      (node (ref "R2") (pin "1") (pinfunction "1_1") (pintype "passive"))
      (node (ref "U3") (pin "13") (pinfunction "DOUT/~{DRDY}_13") (pintype "output"))
    )
    (net (code "84") (name "Net-(U3-SCLK)") (class "Default")
      (node (ref "R4") (pin "1") (pinfunction "1_1") (pintype "passive"))
      (node (ref "U3") (pin "11") (pinfunction "SCLK_11") (pintype "input"))
    )
    (net (code "85") (name "Net-(U3-START)") (class "Default")
      (node (ref "R6") (pin "1") (pinfunction "1_1") (pintype "passive"))
      (node (ref "U3") (pin "9") (pinfunction "START_9") (pintype "input"))
    )
    (net (code "86") (name "Net-(U3-~{CS})") (class "Default")
      (node (ref "R5") (pin "1") (pinfunction "1_1") (pintype "passive"))
      (node (ref "U3") (pin "10") (pinfunction "~{CS}_10") (pintype "input"))
    )
    (net (code "87") (name "Net-(U3-~{DRDY})") (class "Default")
      (node (ref "R1") (pin "1") (pinfunction "1_1") (pintype "passive"))
      (node (ref "U3") (pin "14") (pinfunction "~{DRDY}_14") (pintype "output"))
    )
    (net (code "88") (name "OSC_IN") (class "Default")
      (node (ref "C9") (pin "P$1") (pinfunction "1_P$1") (pintype "passive"))
      (node (ref "U2") (pin "12") (pinfunction "PH0-OSC_IN_12") (pintype "bidirectional"))
      (node (ref "XTAL3") (pin "P$3") (pinfunction "X2_P$3") (pintype "passive"))
    )
    (net (code "89") (name "OSC_OUT") (class "Default")
      (node (ref "C10") (pin "P$1") (pinfunction "1_P$1") (pintype "passive"))
      (node (ref "U2") (pin "13") (pinfunction "PH0-OSC_OUT_13") (pintype "bidirectional"))
      (node (ref "XTAL3") (pin "P$1") (pinfunction "X1_P$1") (pintype "passive"))
    )
    (net (code "90") (name "P0_DUPLEX") (class "Default")
      (node (ref "R29") (pin "2") (pinfunction "2_2") (pintype "passive"))
      (node (ref "U1") (pin "36") (pinfunction "P0_DUPLEX_36") (pintype "bidirectional"))
    )
    (net (code "91") (name "P0_OUTD0_MODE1") (class "Default")
      (node (ref "R31") (pin "1") (pinfunction "1_1") (pintype "passive"))
      (node (ref "U1") (pin "22") (pinfunction "P0_OUTD0/P0_MODE1_22") (pintype "bidirectional"))
    )
    (net (code "92") (name "P0_OUTD1{slash}P0_MODE2") (class "Default")
      (node (ref "R30") (pin "1") (pinfunction "1_1") (pintype "passive"))
      (node (ref "U1") (pin "21") (pinfunction "P0_OUTD1/P0_MODE2_21") (pintype "bidirectional"))
    )
    (net (code "93") (name "P0_OUTD2{slash}P0_MODE3") (class "Default")
      (node (ref "R35") (pin "1") (pinfunction "1_1") (pintype "passive"))
      (node (ref "U1") (pin "16") (pinfunction "P0_OUTD2/P0_MODE3/P1_OUTD0/P1_MODE1_16") (pintype "bidirectional"))
    )
    (net (code "94") (name "P0_OUTER") (class "Default")
      (node (ref "R28") (pin "1") (pinfunction "1_1") (pintype "passive"))
      (node (ref "U1") (pin "19") (pinfunction "P0_OUTER/P0_SPEE/P0_SPEED_19") (pintype "bidirectional"))
    )
    (net (code "95") (name "RIN+") (class "Default")
      (node (ref "L3") (pin "2") (pinfunction "2_2") (pintype "passive"))
      (node (ref "R63") (pin "1") (pinfunction "1_1") (pintype "passive"))
      (node (ref "R64") (pin "1") (pinfunction "1_1") (pintype "passive"))
      (node (ref "R8") (pin "1") (pinfunction "1_1") (pintype "passive"))
      (node (ref "R9") (pin "1") (pinfunction "1_1") (pintype "passive"))
    )
    (net (code "96") (name "RIN-") (class "Default")
      (node (ref "L4") (pin "2") (pinfunction "2_2") (pintype "passive"))
      (node (ref "R65") (pin "1") (pinfunction "1_1") (pintype "passive"))
      (node (ref "R66") (pin "1") (pinfunction "1_1") (pintype "passive"))
      (node (ref "R67") (pin "1") (pinfunction "1_1") (pintype "passive"))
      (node (ref "R68") (pin "1") (pinfunction "1_1") (pintype "passive"))
    )
    (net (code "97") (name "ROUT+") (class "Default")
      (node (ref "C18") (pin "P$1") (pinfunction "1_P$1") (pintype "passive"))
      (node (ref "C21") (pin "P$2") (pinfunction "2_P$2") (pintype "passive"))
      (node (ref "JP3") (pin "1") (pinfunction "1_1") (pintype "passive"))
      (node (ref "JP3") (pin "3") (pinfunction "3_3") (pintype "passive"))
      (node (ref "JP3") (pin "5") (pinfunction "5_5") (pintype "passive"))
      (node (ref "JP3") (pin "7") (pinfunction "7_7") (pintype "passive"))
      (node (ref "U3") (pin "22") (pinfunction "A1_22") (pintype "bidirectional"))
    )
    (net (code "98") (name "ROUT-") (class "Default")
      (node (ref "C18") (pin "P$2") (pinfunction "2_P$2") (pintype "passive"))
      (node (ref "C20") (pin "P$2") (pinfunction "2_P$2") (pintype "passive"))
      (node (ref "JP1") (pin "1") (pinfunction "1_1") (pintype "passive"))
      (node (ref "JP1") (pin "3") (pinfunction "3_3") (pintype "passive"))
      (node (ref "JP1") (pin "5") (pinfunction "5_5") (pintype "passive"))
      (node (ref "JP1") (pin "7") (pinfunction "7_7") (pintype "passive"))
      (node (ref "U3") (pin "23") (pinfunction "A2_23") (pintype "bidirectional"))
    )
    (net (code "99") (name "RXA_N") (class "Default")
      (node (ref "C27") (pin "P$1") (pinfunction "1_P$1") (pintype "passive"))
      (node (ref "J2") (pin "B7") (pinfunction "RD-_B7") (pintype "passive"))
      (node (ref "R11") (pin "1") (pinfunction "1_1") (pintype "passive"))
      (node (ref "U1") (pin "54") (pinfunction "RXNA_54") (pintype "bidirectional"))
    )
    (net (code "100") (name "RXA_P") (class "Default")
      (node (ref "C28") (pin "P$1") (pinfunction "1_P$1") (pintype "passive"))
      (node (ref "J2") (pin "B8") (pinfunction "RD+_B8") (pintype "passive"))
      (node (ref "R12") (pin "1") (pinfunction "1_1") (pintype "passive"))
      (node (ref "U1") (pin "55") (pinfunction "RXPA_55") (pintype "bidirectional"))
    )
    (net (code "101") (name "RXB_N") (class "Default")
      (node (ref "C32") (pin "P$1") (pinfunction "1_P$1") (pintype "passive"))
      (node (ref "J2") (pin "A7") (pinfunction "RD-_A7") (pintype "passive"))
      (node (ref "R15") (pin "1") (pinfunction "1_1") (pintype "passive"))
      (node (ref "U1") (pin "61") (pinfunction "RXNB_61") (pintype "bidirectional"))
    )
    (net (code "102") (name "RXB_P") (class "Default")
      (node (ref "C58") (pin "P$1") (pinfunction "1_P$1") (pintype "passive"))
      (node (ref "J2") (pin "A8") (pinfunction "RD+_A8") (pintype "passive"))
      (node (ref "R16") (pin "1") (pinfunction "1_1") (pintype "passive"))
      (node (ref "U1") (pin "60") (pinfunction "RXPB_60") (pintype "bidirectional"))
    )
    (net (code "103") (name "RXD0") (class "Default")
      (node (ref "R31") (pin "2") (pinfunction "2_2") (pintype "passive"))
      (node (ref "R46") (pin "2") (pinfunction "2_2") (pintype "passive"))
      (node (ref "U2") (pin "33") (pinfunction "PC4_33") (pintype "bidirectional"))
    )
    (net (code "104") (name "RXD1") (class "Default")
      (node (ref "R30") (pin "2") (pinfunction "2_2") (pintype "passive"))
      (node (ref "R36") (pin "2") (pinfunction "2_2") (pintype "passive"))
      (node (ref "U2") (pin "34") (pinfunction "PC5_34") (pintype "bidirectional"))
    )
    (net (code "105") (name "RXD2") (class "Default")
      (node (ref "R34") (pin "2") (pinfunction "2_2") (pintype "passive"))
      (node (ref "R35") (pin "2") (pinfunction "2_2") (pintype "passive"))
      (node (ref "U2") (pin "35") (pinfunction "PB0_35") (pintype "bidirectional"))
    )
    (net (code "106") (name "RXD3") (class "Default")
      (node (ref "R61") (pin "2") (pinfunction "2_2") (pintype "passive"))
      (node (ref "U2") (pin "36") (pinfunction "PB1_36") (pintype "bidirectional"))
    )
    (net (code "107") (name "RX_CLK") (class "Default")
      (node (ref "R27") (pin "2") (pinfunction "2_2") (pintype "passive"))
      (node (ref "R47") (pin "2") (pinfunction "2_2") (pintype "passive"))
      (node (ref "U2") (pin "24") (pinfunction "PA1_24") (pintype "bidirectional"))
    )
    (net (code "108") (name "RX_DV") (class "Default")
      (node (ref "R45") (pin "1") (pinfunction "1_1") (pintype "passive"))
      (node (ref "U1") (pin "23") (pinfunction "P0_OUTDV_23") (pintype "bidirectional"))
      (node (ref "U2") (pin "32") (pinfunction "PA7_32") (pintype "bidirectional"))
    )
    (net (code "109") (name "SCL") (class "Default")
      (node (ref "J3") (pin "3") (pinfunction "3_3") (pintype "bidirectional"))
      (node (ref "R56") (pin "2") (pinfunction "2_2") (pintype "passive"))
      (node (ref "U1") (pin "43") (pinfunction "I2CSCL/EESCL/TCK_43") (pintype "bidirectional"))
      (node (ref "U2") (pin "92") (pinfunction "PB6_92") (pintype "bidirectional"))
    )
    (net (code "110") (name "SCLK") (class "Default")
      (node (ref "R4") (pin "2") (pinfunction "2_2") (pintype "passive"))
    )
    (net (code "111") (name "SDA") (class "Default")
      (node (ref "J3") (pin "2") (pinfunction "2_2") (pintype "bidirectional"))
      (node (ref "R57") (pin "2") (pinfunction "2_2") (pintype "passive"))
      (node (ref "U1") (pin "42") (pinfunction "I2CSDA/EESDA/TMS_42") (pintype "bidirectional"))
      (node (ref "U2") (pin "93") (pinfunction "PB7_93") (pintype "bidirectional"))
    )
    (net (code "112") (name "START") (class "Default")
      (node (ref "R6") (pin "2") (pinfunction "2_2") (pintype "passive"))
    )
    (net (code "113") (name "SWCLK") (class "Default")
      (node (ref "J1") (pin "06") (pinfunction "06_06") (pintype "passive"))
      (node (ref "J4") (pin "1") (pinfunction "1_1") (pintype "bidirectional"))
      (node (ref "U2") (pin "76") (pinfunction "PA14_76") (pintype "bidirectional"))
    )
    (net (code "114") (name "SWDIO") (class "Default")
      (node (ref "J1") (pin "04") (pinfunction "04_04") (pintype "passive"))
      (node (ref "J4") (pin "3") (pinfunction "3_3") (pintype "bidirectional"))
      (node (ref "U2") (pin "72") (pinfunction "PA13_72") (pintype "bidirectional"))
    )
    (net (code "115") (name "SWO") (class "Default")
      (node (ref "J1") (pin "08") (pinfunction "08_08") (pintype "passive"))
      (node (ref "J4") (pin "5") (pinfunction "5_5") (pintype "bidirectional"))
      (node (ref "U2") (pin "89") (pinfunction "PB3_89") (pintype "bidirectional"))
    )
    (net (code "116") (name "TXA_N") (class "Default")
      (node (ref "C29") (pin "P$1") (pinfunction "1_P$1") (pintype "passive"))
      (node (ref "J2") (pin "B3") (pinfunction "TD-_B3") (pintype "passive"))
      (node (ref "R13") (pin "1") (pinfunction "1_1") (pintype "passive"))
      (node (ref "U1") (pin "52") (pinfunction "TXNA_52") (pintype "bidirectional"))
    )
    (net (code "117") (name "TXA_P") (class "Default")
      (node (ref "C30") (pin "P$1") (pinfunction "1_P$1") (pintype "passive"))
      (node (ref "J2") (pin "B4") (pinfunction "TD+_B4") (pintype "passive"))
      (node (ref "R14") (pin "1") (pinfunction "1_1") (pintype "passive"))
      (node (ref "U1") (pin "53") (pinfunction "TXPA_53") (pintype "bidirectional"))
    )
    (net (code "118") (name "TXB_N") (class "Default")
      (node (ref "C59") (pin "P$1") (pinfunction "1_P$1") (pintype "passive"))
      (node (ref "J2") (pin "A3") (pinfunction "TD-_A3") (pintype "passive"))
      (node (ref "R17") (pin "1") (pinfunction "1_1") (pintype "passive"))
      (node (ref "U1") (pin "63") (pinfunction "TXNB_63") (pintype "bidirectional"))
    )
    (net (code "119") (name "TXB_P") (class "Default")
      (node (ref "C60") (pin "P$1") (pinfunction "1_P$1") (pintype "passive"))
      (node (ref "J2") (pin "A4") (pinfunction "TD+_A4") (pintype "passive"))
      (node (ref "R18") (pin "1") (pinfunction "1_1") (pintype "passive"))
      (node (ref "U1") (pin "62") (pinfunction "TXPB_62") (pintype "bidirectional"))
    )
    (net (code "120") (name "TXD0") (class "Default")
      (node (ref "R26") (pin "2") (pinfunction "2_2") (pintype "passive"))
      (node (ref "U2") (pin "51") (pinfunction "PB12_51") (pintype "bidirectional"))
    )
    (net (code "121") (name "TXD1") (class "Default")
      (node (ref "R25") (pin "2") (pinfunction "2_2") (pintype "passive"))
      (node (ref "U2") (pin "52") (pinfunction "PB13_52") (pintype "bidirectional"))
    )
    (net (code "122") (name "TXD2") (class "Default")
      (node (ref "R23") (pin "2") (pinfunction "2_2") (pintype "passive"))
      (node (ref "U2") (pin "17") (pinfunction "PC2_17") (pintype "bidirectional"))
    )
    (net (code "123") (name "TXD3") (class "Default")
      (node (ref "R24") (pin "2") (pinfunction "2_2") (pintype "passive"))
      (node (ref "U2") (pin "95") (pinfunction "PB8_95") (pintype "bidirectional"))
    )
    (net (code "124") (name "TX_CLK") (class "Default")
      (node (ref "R22") (pin "2") (pinfunction "2_2") (pintype "passive"))
      (node (ref "U2") (pin "18") (pinfunction "PC3_18") (pintype "bidirectional"))
    )
    (net (code "125") (name "TX_EN") (class "Default")
      (node (ref "R52") (pin "2") (pinfunction "2_2") (pintype "passive"))
      (node (ref "U2") (pin "48") (pinfunction "PB11_48") (pintype "bidirectional"))
    )
    (net (code "126") (name "USART1_RX") (class "Default")
      (node (ref "R49") (pin "1") (pinfunction "1_1") (pintype "passive"))
      (node (ref "U2") (pin "69") (pinfunction "PA10_69") (pintype "bidirectional"))
    )
    (net (code "127") (name "USART1_TX") (class "Default")
      (node (ref "R50") (pin "1") (pinfunction "1_1") (pintype "passive"))
      (node (ref "U2") (pin "68") (pinfunction "PA9_68") (pintype "bidirectional"))
    )
    (net (code "128") (name "VDD12TX") (class "Default")
      (node (ref "C66") (pin "P$1") (pinfunction "1_P$1") (pintype "passive"))
      (node (ref "C67") (pin "P$1") (pinfunction "1_P$1") (pintype "passive"))
      (node (ref "C68") (pin "P$1") (pinfunction "1_P$1") (pintype "passive"))
      (node (ref "C69") (pin "P$1") (pinfunction "1_P$1") (pintype "passive"))
      (node (ref "FB11") (pin "2") (pinfunction "2_2") (pintype "passive"))
      (node (ref "U1") (pin "56") (pinfunction "VDD12TX1_56") (pintype "bidirectional"))
      (node (ref "U1") (pin "59") (pinfunction "VDD12TX2_59") (pintype "bidirectional"))
    )
    (net (code "129") (name "VDD33BIAS") (class "Default")
      (node (ref "C65") (pin "P$1") (pinfunction "1_P$1") (pintype "passive"))
      (node (ref "FB12") (pin "1") (pinfunction "1_1") (pintype "passive"))
      (node (ref "U1") (pin "58") (pinfunction "VDD33BIAS_58") (pintype "bidirectional"))
    )
    (net (code "130") (name "VDD33TXRX1") (class "Default")
      (node (ref "C63") (pin "P$1") (pinfunction "1_P$1") (pintype "passive"))
      (node (ref "FB10") (pin "1") (pinfunction "1_1") (pintype "passive"))
      (node (ref "FB7") (pin "2") (pinfunction "2_2") (pintype "passive"))
      (node (ref "U1") (pin "51") (pinfunction "VDD33TXRX1_51") (pintype "bidirectional"))
    )
    (net (code "131") (name "VDD33TXRX1-B") (class "Default")
      (node (ref "FB7") (pin "1") (pinfunction "1_1") (pintype "passive"))
      (node (ref "R11") (pin "2") (pinfunction "2_2") (pintype "passive"))
      (node (ref "R12") (pin "2") (pinfunction "2_2") (pintype "passive"))
      (node (ref "R13") (pin "2") (pinfunction "2_2") (pintype "passive"))
      (node (ref "R14") (pin "2") (pinfunction "2_2") (pintype "passive"))
      (node (ref "R59") (pin "2") (pinfunction "2_2") (pintype "passive"))
    )
    (net (code "132") (name "VDD33TXRX1-C") (class "Default")
      (node (ref "C26") (pin "P$1") (pinfunction "1_P$1") (pintype "passive"))
      (node (ref "J2") (pin "B5") (pinfunction "P4_B5") (pintype "passive"))
      (node (ref "J2") (pin "B6") (pinfunction "P5_B6") (pintype "passive"))
      (node (ref "R59") (pin "1") (pinfunction "1_1") (pintype "passive"))
    )
    (net (code "133") (name "VDD33TXRX2") (class "Default")
      (node (ref "C64") (pin "P$1") (pinfunction "1_P$1") (pintype "passive"))
      (node (ref "FB8") (pin "2") (pinfunction "2_2") (pintype "passive"))
      (node (ref "FB9") (pin "1") (pinfunction "1_1") (pintype "passive"))
      (node (ref "U1") (pin "64") (pinfunction "VDD33TXRX2_64") (pintype "bidirectional"))
    )
    (net (code "134") (name "VDD33TXRX2-B") (class "Default")
      (node (ref "FB8") (pin "1") (pinfunction "1_1") (pintype "passive"))
      (node (ref "R15") (pin "2") (pinfunction "2_2") (pintype "passive"))
      (node (ref "R16") (pin "2") (pinfunction "2_2") (pintype "passive"))
      (node (ref "R17") (pin "2") (pinfunction "2_2") (pintype "passive"))
      (node (ref "R18") (pin "2") (pinfunction "2_2") (pintype "passive"))
      (node (ref "R58") (pin "2") (pinfunction "2_2") (pintype "passive"))
    )
    (net (code "135") (name "VDD33TXRX2-C") (class "Default")
      (node (ref "C31") (pin "P$1") (pinfunction "1_P$1") (pintype "passive"))
      (node (ref "J2") (pin "A5") (pinfunction "P4_A5") (pintype "passive"))
      (node (ref "J2") (pin "A6") (pinfunction "P5_A6") (pintype "passive"))
      (node (ref "R58") (pin "1") (pinfunction "1_1") (pintype "passive"))
    )
    (net (code "136") (name "VDDCR") (class "Default")
      (node (ref "C76") (pin "P$1") (pinfunction "1_P$1") (pintype "passive"))
      (node (ref "C77") (pin "P$1") (pinfunction "1_P$1") (pintype "passive"))
      (node (ref "C78") (pin "P$1") (pinfunction "1_P$1") (pintype "passive"))
      (node (ref "C79") (pin "P$1") (pinfunction "1_P$1") (pintype "passive"))
      (node (ref "FB11") (pin "1") (pinfunction "1_1") (pintype "passive"))
      (node (ref "U1") (pin "24") (pinfunction "VDDCR_24") (pintype "bidirectional"))
      (node (ref "U1") (pin "38") (pinfunction "VDDCR_38") (pintype "bidirectional"))
      (node (ref "U1") (pin "6") (pinfunction "VDDCR_6") (pintype "bidirectional"))
    )
    (net (code "137") (name "unconnected-(J1-Pad01)") (class "Default")
      (node (ref "J1") (pin "01") (pinfunction "01_01") (pintype "passive"))
    )
    (net (code "138") (name "unconnected-(J1-Pad02)") (class "Default")
      (node (ref "J1") (pin "02") (pinfunction "02_02") (pintype "passive"))
    )
    (net (code "139") (name "unconnected-(J1-Pad09)") (class "Default")
      (node (ref "J1") (pin "09") (pinfunction "09_09") (pintype "passive"))
    )
    (net (code "140") (name "unconnected-(J1-Pad10)") (class "Default")
      (node (ref "J1") (pin "10") (pinfunction "10_10") (pintype "passive"))
    )
    (net (code "141") (name "unconnected-(J1-Pad11)") (class "Default")
      (node (ref "J1") (pin "11") (pinfunction "11_11") (pintype "passive"))
    )
    (net (code "142") (name "unconnected-(R51-Pad2)") (class "Default")
      (node (ref "R51") (pin "2") (pinfunction "2_2") (pintype "passive"))
    )
    (net (code "143") (name "unconnected-(U1-GPIO6-Pad13)") (class "Default")
      (node (ref "U1") (pin "13") (pinfunction "GPIO6_13") (pintype "bidirectional"))
    )
    (net (code "144") (name "unconnected-(U1-OSCVDD12-Pad3)") (class "Default")
      (node (ref "U1") (pin "3") (pinfunction "OSCVDD12_3") (pintype "bidirectional"))
    )
    (net (code "145") (name "unconnected-(U1-PGPIO7-Pad12)") (class "Default")
      (node (ref "U1") (pin "12") (pinfunction "PGPIO7_12") (pintype "bidirectional"))
    )
    (net (code "146") (name "unconnected-(U1-RESERVED{slash}P1_OUTDV-Pad35)") (class "Default")
      (node (ref "U1") (pin "35") (pinfunction "RESERVED/P1_OUTDV_35") (pintype "bidirectional"))
    )
    (net (code "147") (name "unconnected-(U2-PA4-Pad29)") (class "Default")
      (node (ref "U2") (pin "29") (pinfunction "PA4_29") (pintype "bidirectional"))
    )
    (net (code "148") (name "unconnected-(U2-PA5-Pad30)") (class "Default")
      (node (ref "U2") (pin "30") (pinfunction "PA5_30") (pintype "bidirectional"))
    )
    (net (code "149") (name "unconnected-(U2-PA6-Pad31)") (class "Default")
      (node (ref "U2") (pin "31") (pinfunction "PA6_31") (pintype "bidirectional"))
    )
    (net (code "150") (name "unconnected-(U2-PA8-Pad67)") (class "Default")
      (node (ref "U2") (pin "67") (pinfunction "PA8_67") (pintype "bidirectional"))
    )
    (net (code "151") (name "unconnected-(U2-PA11-Pad70)") (class "Default")
      (node (ref "U2") (pin "70") (pinfunction "PA11_70") (pintype "bidirectional"))
    )
    (net (code "152") (name "unconnected-(U2-PA15-Pad77)") (class "Default")
      (node (ref "U2") (pin "77") (pinfunction "PA15_77") (pintype "bidirectional"))
    )
    (net (code "153") (name "unconnected-(U2-PB4-Pad90)") (class "Default")
      (node (ref "U2") (pin "90") (pinfunction "PB4_90") (pintype "bidirectional"))
    )
    (net (code "154") (name "unconnected-(U2-PB9-Pad96)") (class "Default")
      (node (ref "U2") (pin "96") (pinfunction "PB9_96") (pintype "bidirectional"))
    )
    (net (code "155") (name "unconnected-(U2-PB14-Pad53)") (class "Default")
      (node (ref "U2") (pin "53") (pinfunction "PB14_53") (pintype "bidirectional"))
    )
    (net (code "156") (name "unconnected-(U2-PB15-Pad54)") (class "Default")
      (node (ref "U2") (pin "54") (pinfunction "PB15_54") (pintype "bidirectional"))
    )
    (net (code "157") (name "unconnected-(U2-PC0-Pad15)") (class "Default")
      (node (ref "U2") (pin "15") (pinfunction "PC0_15") (pintype "bidirectional"))
    )
    (net (code "158") (name "unconnected-(U2-PC6-Pad63)") (class "Default")
      (node (ref "U2") (pin "63") (pinfunction "PC6_63") (pintype "bidirectional"))
    )
    (net (code "159") (name "unconnected-(U2-PC7-Pad64)") (class "Default")
      (node (ref "U2") (pin "64") (pinfunction "PC7_64") (pintype "bidirectional"))
    )
    (net (code "160") (name "unconnected-(U2-PC8-Pad65)") (class "Default")
      (node (ref "U2") (pin "65") (pinfunction "PC8_65") (pintype "bidirectional"))
    )
    (net (code "161") (name "unconnected-(U2-PC9-Pad66)") (class "Default")
      (node (ref "U2") (pin "66") (pinfunction "PC9_66") (pintype "bidirectional"))
    )
    (net (code "162") (name "unconnected-(U2-PC10-Pad78)") (class "Default")
      (node (ref "U2") (pin "78") (pinfunction "PC10_78") (pintype "bidirectional"))
    )
    (net (code "163") (name "unconnected-(U2-PC11-Pad79)") (class "Default")
      (node (ref "U2") (pin "79") (pinfunction "PC11_79") (pintype "bidirectional"))
    )
    (net (code "164") (name "unconnected-(U2-PC12-Pad80)") (class "Default")
      (node (ref "U2") (pin "80") (pinfunction "PC12_80") (pintype "bidirectional"))
    )
    (net (code "165") (name "unconnected-(U2-PC13-RTC_AF1-Pad7)") (class "Default")
      (node (ref "U2") (pin "7") (pinfunction "PC13-RTC_AF1_7") (pintype "bidirectional"))
    )
    (net (code "166") (name "unconnected-(U2-PC14-OSC32_IN-Pad8)") (class "Default")
      (node (ref "U2") (pin "8") (pinfunction "PC14-OSC32_IN_8") (pintype "bidirectional"))
    )
    (net (code "167") (name "unconnected-(U2-PC14-OSC32_OUT-Pad9)") (class "Default")
      (node (ref "U2") (pin "9") (pinfunction "PC14-OSC32_OUT_9") (pintype "bidirectional"))
    )
    (net (code "168") (name "unconnected-(U2-PD0-Pad81)") (class "Default")
      (node (ref "U2") (pin "81") (pinfunction "PD0_81") (pintype "bidirectional"))
    )
    (net (code "169") (name "unconnected-(U2-PD1-Pad82)") (class "Default")
      (node (ref "U2") (pin "82") (pinfunction "PD1_82") (pintype "bidirectional"))
    )
    (net (code "170") (name "unconnected-(U2-PD2-Pad83)") (class "Default")
      (node (ref "U2") (pin "83") (pinfunction "PD2_83") (pintype "bidirectional"))
    )
    (net (code "171") (name "unconnected-(U2-PD3-Pad84)") (class "Default")
      (node (ref "U2") (pin "84") (pinfunction "PD3_84") (pintype "bidirectional"))
    )
    (net (code "172") (name "unconnected-(U2-PD4-Pad85)") (class "Default")
      (node (ref "U2") (pin "85") (pinfunction "PD4_85") (pintype "bidirectional"))
    )
    (net (code "173") (name "unconnected-(U2-PD5-Pad86)") (class "Default")
      (node (ref "U2") (pin "86") (pinfunction "PD5_86") (pintype "bidirectional"))
    )
    (net (code "174") (name "unconnected-(U2-PD6-Pad87)") (class "Default")
      (node (ref "U2") (pin "87") (pinfunction "PD6_87") (pintype "bidirectional"))
    )
    (net (code "175") (name "unconnected-(U2-PD7-Pad88)") (class "Default")
      (node (ref "U2") (pin "88") (pinfunction "PD7_88") (pintype "bidirectional"))
    )
    (net (code "176") (name "unconnected-(U2-PD8-Pad55)") (class "Default")
      (node (ref "U2") (pin "55") (pinfunction "PD8_55") (pintype "bidirectional"))
    )
    (net (code "177") (name "unconnected-(U2-PD9-Pad56)") (class "Default")
      (node (ref "U2") (pin "56") (pinfunction "PD9_56") (pintype "bidirectional"))
    )
    (net (code "178") (name "unconnected-(U2-PD10-Pad57)") (class "Default")
      (node (ref "U2") (pin "57") (pinfunction "PD10_57") (pintype "bidirectional"))
    )
    (net (code "179") (name "unconnected-(U2-PD11-Pad58)") (class "Default")
      (node (ref "U2") (pin "58") (pinfunction "PD11_58") (pintype "bidirectional"))
    )
    (net (code "180") (name "unconnected-(U2-PD12-Pad59)") (class "Default")
      (node (ref "U2") (pin "59") (pinfunction "PD12_59") (pintype "bidirectional"))
    )
    (net (code "181") (name "unconnected-(U2-PD13-Pad60)") (class "Default")
      (node (ref "U2") (pin "60") (pinfunction "PD13_60") (pintype "bidirectional"))
    )
    (net (code "182") (name "unconnected-(U2-PD14-Pad61)") (class "Default")
      (node (ref "U2") (pin "61") (pinfunction "PD14_61") (pintype "bidirectional"))
    )
    (net (code "183") (name "unconnected-(U2-PD15-Pad62)") (class "Default")
      (node (ref "U2") (pin "62") (pinfunction "PD15_62") (pintype "bidirectional"))
    )
    (net (code "184") (name "unconnected-(U2-PE0-Pad97)") (class "Default")
      (node (ref "U2") (pin "97") (pinfunction "PE0_97") (pintype "bidirectional"))
    )
    (net (code "185") (name "unconnected-(U2-PE1-Pad98)") (class "Default")
      (node (ref "U2") (pin "98") (pinfunction "PE1_98") (pintype "bidirectional"))
    )
    (net (code "186") (name "unconnected-(U2-PE2-Pad1)") (class "Default")
      (node (ref "U2") (pin "1") (pinfunction "PE2_1") (pintype "bidirectional"))
    )
    (net (code "187") (name "unconnected-(U2-PE3-Pad2)") (class "Default")
      (node (ref "U2") (pin "2") (pinfunction "PE3_2") (pintype "bidirectional"))
    )
    (net (code "188") (name "unconnected-(U2-PE4-Pad3)") (class "Default")
      (node (ref "U2") (pin "3") (pinfunction "PE4_3") (pintype "bidirectional"))
    )
    (net (code "189") (name "unconnected-(U2-PE7-Pad38)") (class "Default")
      (node (ref "U2") (pin "38") (pinfunction "PE7_38") (pintype "bidirectional"))
    )
    (net (code "190") (name "unconnected-(U2-PE8-Pad39)") (class "Default")
      (node (ref "U2") (pin "39") (pinfunction "PE8_39") (pintype "bidirectional"))
    )
    (net (code "191") (name "unconnected-(U2-PE9-Pad40)") (class "Default")
      (node (ref "U2") (pin "40") (pinfunction "PE9_40") (pintype "bidirectional"))
    )
    (net (code "192") (name "unconnected-(U2-PE10-Pad41)") (class "Default")
      (node (ref "U2") (pin "41") (pinfunction "PE10_41") (pintype "bidirectional"))
    )
    (net (code "193") (name "unconnected-(U2-PE11-Pad42)") (class "Default")
      (node (ref "U2") (pin "42") (pinfunction "PE11_42") (pintype "bidirectional"))
    )
    (net (code "194") (name "unconnected-(U2-PE12-Pad43)") (class "Default")
      (node (ref "U2") (pin "43") (pinfunction "PE12_43") (pintype "bidirectional"))
    )
    (net (code "195") (name "unconnected-(U2-PE13-Pad44)") (class "Default")
      (node (ref "U2") (pin "44") (pinfunction "PE13_44") (pintype "bidirectional"))
    )
    (net (code "196") (name "unconnected-(U2-PE14-Pad45)") (class "Default")
      (node (ref "U2") (pin "45") (pinfunction "PE14_45") (pintype "bidirectional"))
    )
    (net (code "197") (name "unconnected-(U2-PE15-Pad46)") (class "Default")
      (node (ref "U2") (pin "46") (pinfunction "PE15_46") (pintype "bidirectional"))
    )
    (net (code "198") (name "unconnected-(U2-RFU-Pad99)") (class "Default")
      (node (ref "U2") (pin "99") (pinfunction "RFU_99") (pintype "bidirectional"))
    )
    (net (code "199") (name "unconnected-(U2-VBAT-Pad6)") (class "Default")
      (node (ref "U2") (pin "6") (pinfunction "VBAT_6") (pintype "bidirectional"))
    )
    (net (code "200") (name "unconnected-(U3-A6-Pad27)") (class "Default")
      (node (ref "U3") (pin "27") (pinfunction "A6_27") (pintype "bidirectional"))
    )
    (net (code "201") (name "~{CS}") (class "Default")
      (node (ref "R5") (pin "2") (pinfunction "2_2") (pintype "passive"))
    )
    (net (code "202") (name "~{DRDY}") (class "Default")
      (node (ref "R1") (pin "2") (pinfunction "2_2") (pintype "passive"))
    )
    (net (code "203") (name "~{ETH_RST}") (class "Default")
      (node (ref "U1") (pin "11") (pinfunction "RST#_11") (pintype "bidirectional"))
      (node (ref "U2") (pin "4") (pinfunction "PE5_4") (pintype "bidirectional"))
    )
  )
)
